# zx80_SD_12_smd_build006_4_STM32.net
KiCad netlist of a schematic drawn in EAGLE
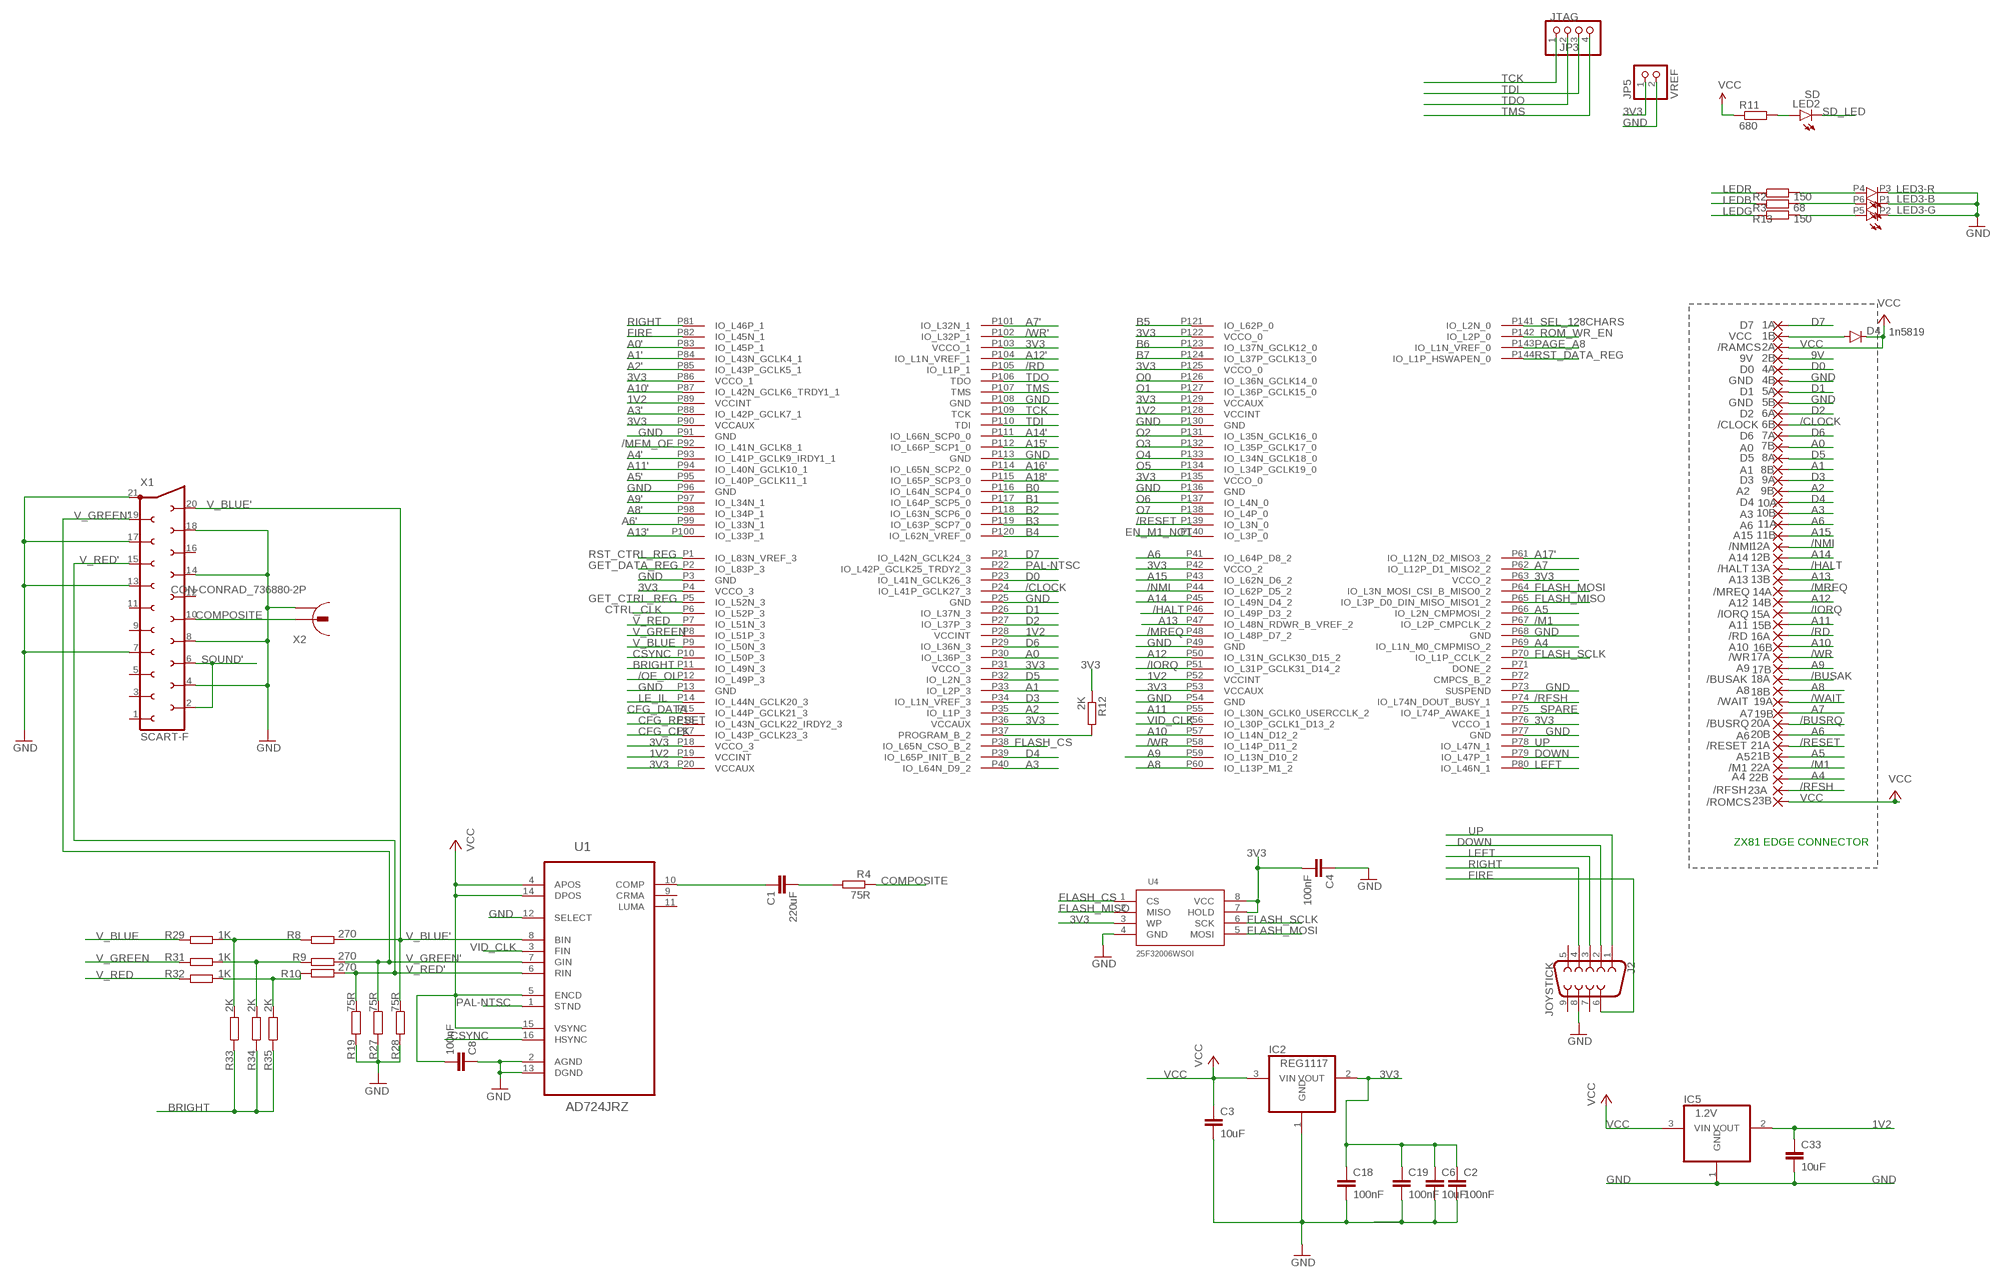
[diagram p0: schematic, sheet 1, part 1 of 2]
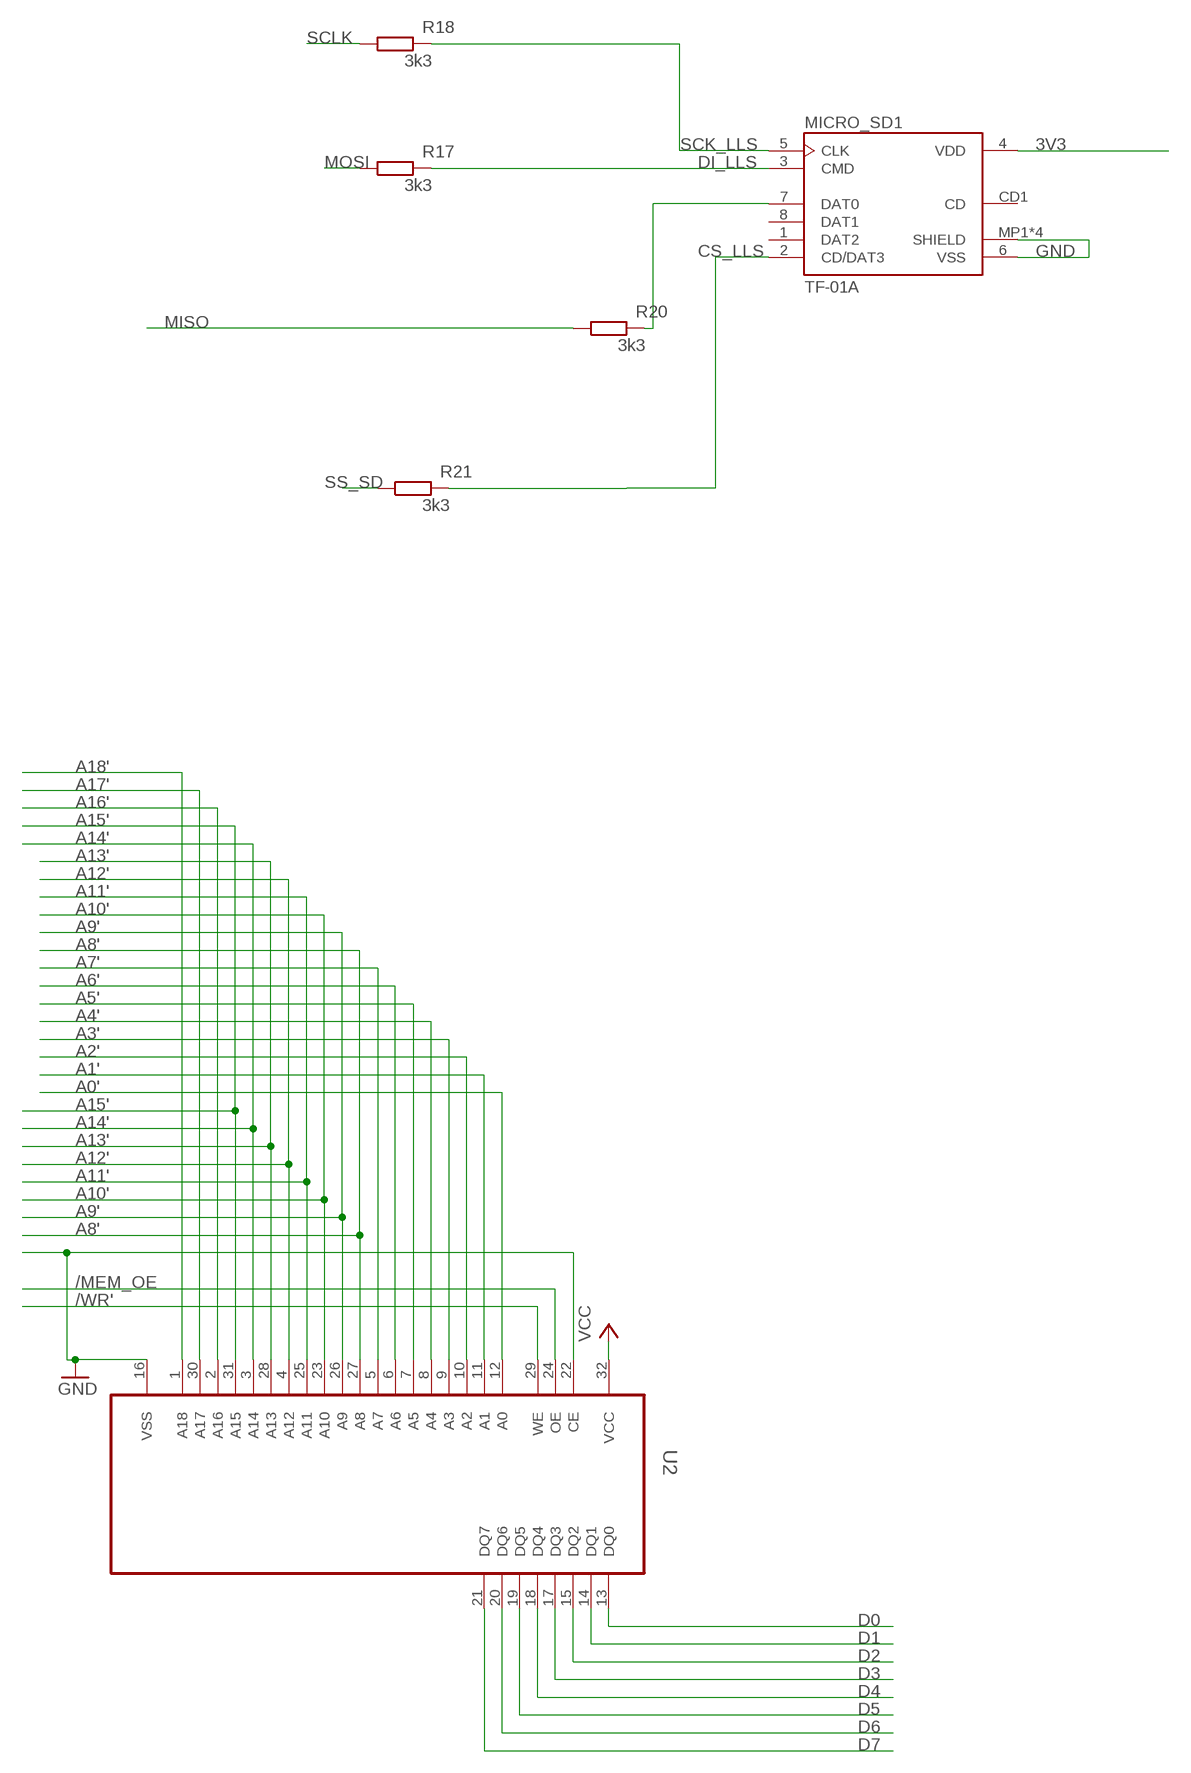
[diagram p1: schematic, sheet 1, part 2 of 2]
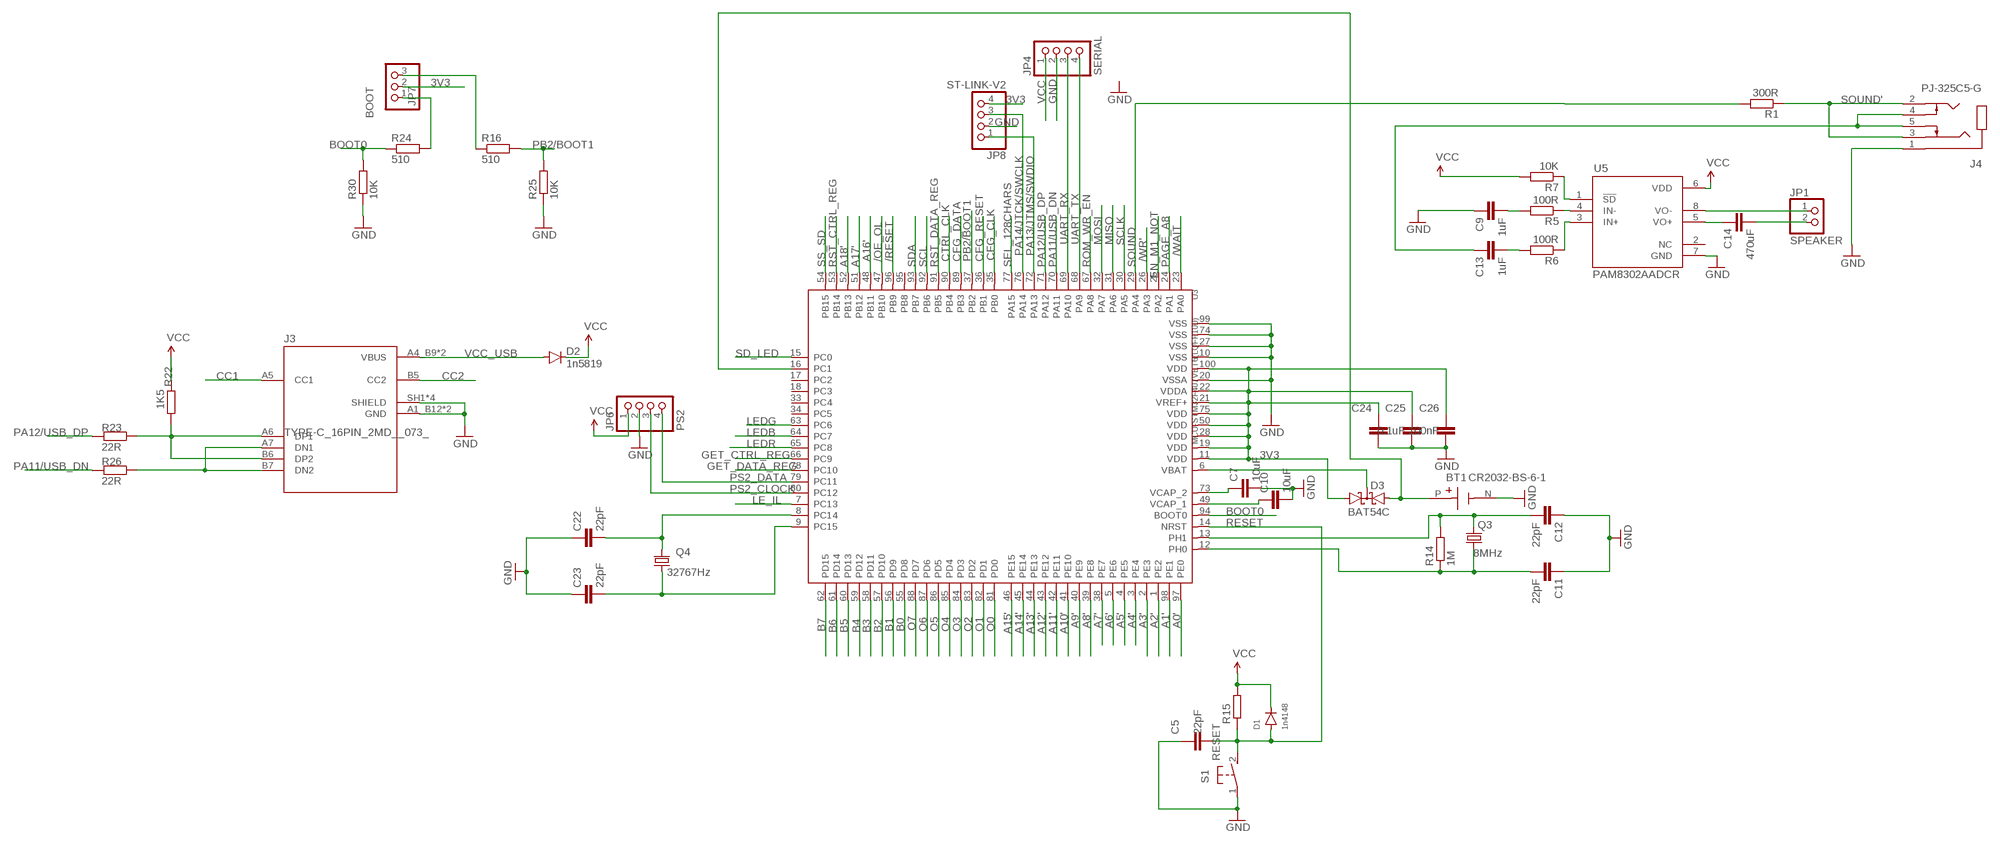
[diagram p2: schematic, sheet 2]

(export (version "E")
  (design (tool "Eeschema 10.0.6"))
  (components
    (comp (ref "BT1")
      (value "CR2032-BS-6-1")
      (footprint "eagle-import:BAT_CR2032-BS-6-1")
      (fields (field (name "MF") "Shenzhen Q&J Electronics Co. Ltd"))
      (libsource (lib "eagle-import") (part "CR2032-BS-6-1"))
    )
    (comp (ref "C5")
      (value "22pF")
      (footprint "eagle-import:C0603")
      (libsource (lib "eagle-import") (part "C-EUC0603"))
    )
    (comp (ref "C7")
      (value "10uF")
      (footprint "eagle-import:C1206")
      (libsource (lib "eagle-import") (part "C-EUC1206"))
    )
    (comp (ref "C9")
      (value "1uF")
      (footprint "eagle-import:C0603")
      (libsource (lib "eagle-import") (part "C-EUC0603"))
    )
    (comp (ref "C10")
      (value "10uF")
      (footprint "eagle-import:C1206")
      (libsource (lib "eagle-import") (part "C-EUC1206"))
    )
    (comp (ref "C11")
      (value "22pF")
      (footprint "eagle-import:C0603")
      (libsource (lib "eagle-import") (part "C-EUC0603"))
    )
    (comp (ref "C12")
      (value "22pF")
      (footprint "eagle-import:C0603")
      (libsource (lib "eagle-import") (part "C-EUC0603"))
    )
    (comp (ref "C13")
      (value "1uF")
      (footprint "eagle-import:C0603")
      (libsource (lib "eagle-import") (part "C-EUC0603"))
    )
    (comp (ref "C14")
      (value "470uF")
      (footprint "eagle-import:C0603")
      (libsource (lib "eagle-import") (part "C-EUC0603"))
    )
    (comp (ref "C22")
      (value "22pF")
      (footprint "eagle-import:C0603")
      (libsource (lib "eagle-import") (part "C-EUC0603"))
    )
    (comp (ref "C23")
      (value "22pF")
      (footprint "eagle-import:C0603")
      (libsource (lib "eagle-import") (part "C-EUC0603"))
    )
    (comp (ref "C24")
      (value "0.1uF")
      (footprint "eagle-import:C0603")
      (libsource (lib "eagle-import") (part "C-EUC0603"))
    )
    (comp (ref "C25")
      (value "0.1uF")
      (footprint "eagle-import:C0603")
      (libsource (lib "eagle-import") (part "C-EUC0603"))
    )
    (comp (ref "C26")
      (value "100nF")
      (footprint "eagle-import:C0603")
      (libsource (lib "eagle-import") (part "C-EUC0603"))
    )
    (comp (ref "D1")
      (value "1n4148")
      (footprint "eagle-import:SOD123")
      (libsource (lib "eagle-import") (part "DIODE-SOD123"))
    )
    (comp (ref "D2")
      (value "1n5819")
      (footprint "eagle-import:SOD323-W")
      (libsource (lib "eagle-import") (part "DIODE-SOD323-W"))
    )
    (comp (ref "D3")
      (value "BAT54C")
      (footprint "eagle-import:SOT23")
      (libsource (lib "eagle-import") (part "BAT54C"))
    )
    (comp (ref "J3")
      (value "TYPE-C_16PIN_2MD__073_")
      (footprint "eagle-import:SHOUHAN_TYPE-C_16PIN_2MD__073_")
      (fields (field (name "MF") "Shouhan") (field (name "MP") "TYPE-C 16PIN 2MD (073)"))
      (libsource (lib "eagle-import") (part "TYPE-C_16PIN_2MD__073_"))
    )
    (comp (ref "J4")
      (value "PJ-325C5-G")
      (footprint "eagle-import:XKB_PJ-325C5-G")
      (fields (field (name "MF") "XKB Connection"))
      (libsource (lib "eagle-import") (part "PJ-325C5-G"))
    )
    (comp (ref "JP1")
      (value "SPEAKER")
      (footprint "eagle-import:1X02")
      (libsource (lib "eagle-import") (part "PINHD-1X2"))
    )
    (comp (ref "JP4")
      (value "SERIAL")
      (footprint "eagle-import:1X04")
      (libsource (lib "eagle-import") (part "PINHD-1X4"))
    )
    (comp (ref "JP6")
      (value "PS2")
      (footprint "eagle-import:1X04")
      (libsource (lib "eagle-import") (part "PINHD-1X4"))
    )
    (comp (ref "JP7")
      (value "BOOT")
      (footprint "eagle-import:1X03")
      (libsource (lib "eagle-import") (part "PINHD-1X3"))
    )
    (comp (ref "JP8")
      (value "ST-LINK-V2")
      (footprint "eagle-import:1X04")
      (libsource (lib "eagle-import") (part "PINHD-1X4"))
    )
    (comp (ref "Q3")
      (value "8MHz")
      (footprint "eagle-import:3.2X2.5_KX-7")
      (libsource (lib "eagle-import") (part "KX-7"))
    )
    (comp (ref "Q4")
      (value "32767Hz")
      (footprint "eagle-import:3.2X1.5")
      (libsource (lib "eagle-import") (part "KX-327-NHT"))
    )
    (comp (ref "R1")
      (value "300R")
      (footprint "eagle-import:R0603")
      (libsource (lib "eagle-import") (part "R-EU_R0603"))
    )
    (comp (ref "R5")
      (value "100R")
      (footprint "eagle-import:R0603")
      (libsource (lib "eagle-import") (part "R-EU_R0603"))
    )
    (comp (ref "R6")
      (value "100R")
      (footprint "eagle-import:R0603")
      (libsource (lib "eagle-import") (part "R-EU_R0603"))
    )
    (comp (ref "R7")
      (value "10K")
      (footprint "eagle-import:R0603")
      (libsource (lib "eagle-import") (part "R-EU_R0603"))
    )
    (comp (ref "R14")
      (value "1M")
      (footprint "eagle-import:R0603")
      (libsource (lib "eagle-import") (part "R-EU_R0603"))
    )
    (comp (ref "R15")
      (value "3K3")
      (footprint "eagle-import:R0603")
      (libsource (lib "eagle-import") (part "R-EU_R0603"))
    )
    (comp (ref "R16")
      (value "510")
      (footprint "eagle-import:R0603")
      (libsource (lib "eagle-import") (part "R-EU_R0603"))
    )
    (comp (ref "R22")
      (value "1K5")
      (footprint "eagle-import:R0603")
      (libsource (lib "eagle-import") (part "R-EU_R0603"))
    )
    (comp (ref "R23")
      (value "22R")
      (footprint "eagle-import:R0603")
      (libsource (lib "eagle-import") (part "R-EU_R0603"))
    )
    (comp (ref "R24")
      (value "510")
      (footprint "eagle-import:R0603")
      (libsource (lib "eagle-import") (part "R-EU_R0603"))
    )
    (comp (ref "R25")
      (value "10K")
      (footprint "eagle-import:R0603")
      (libsource (lib "eagle-import") (part "R-EU_R0603"))
    )
    (comp (ref "R26")
      (value "22R")
      (footprint "eagle-import:R0603")
      (libsource (lib "eagle-import") (part "R-EU_R0603"))
    )
    (comp (ref "R30")
      (value "10K")
      (footprint "eagle-import:R0603")
      (libsource (lib "eagle-import") (part "R-EU_R0603"))
    )
    (comp (ref "S1")
      (value "RESET")
      (footprint "eagle-import:B3F-31XX")
      (fields (field (name "MPN") "B3F-3100"))
      (libsource (lib "eagle-import") (part "31-XX"))
    )
    (comp (ref "U3")
      (value "MCU-STM32F407VET6(LQFP100)")
      (footprint "eagle-import:LQFP100-0.5-13.8X13.8MM")
      (fields (field (name "MF") "STMicroelectronics") (field (name "MP") "STM32F407VET6"))
      (libsource (lib "eagle-import") (part "MCU-STM32F407VET6(LQFP100)"))
    )
    (comp (ref "U5")
      (value "PAM8302AADCR")
      (footprint "eagle-import:SOIC127P600X170-8N")
      (fields (field (name "MF") "Diodes Inc."))
      (libsource (lib "eagle-import") (part "PAM8302AADCR"))
    )
    (comp (ref "1A")
      (value "D7")
      (footprint "eagle-import:EDGEPIN")
      (libsource (lib "eagle-import") (part "SMD2EDGEPIN"))
    )
    (comp (ref "1B")
      (value "VCC")
      (footprint "eagle-import:EDGEPIN")
      (libsource (lib "eagle-import") (part "SMD2EDGEPIN"))
    )
    (comp (ref "2A")
      (value "/RAMCS")
      (footprint "eagle-import:EDGEPIN")
      (libsource (lib "eagle-import") (part "SMD2EDGEPIN"))
    )
    (comp (ref "2B")
      (value "9V")
      (footprint "eagle-import:EDGEPIN")
      (libsource (lib "eagle-import") (part "SMD2EDGEPIN"))
    )
    (comp (ref "4A")
      (value "D0")
      (footprint "eagle-import:EDGEPIN")
      (libsource (lib "eagle-import") (part "SMD2EDGEPIN"))
    )
    (comp (ref "4B")
      (value "GND")
      (footprint "eagle-import:EDGEPIN")
      (libsource (lib "eagle-import") (part "SMD2EDGEPIN"))
    )
    (comp (ref "5A")
      (value "D1")
      (footprint "eagle-import:EDGEPIN")
      (libsource (lib "eagle-import") (part "SMD2EDGEPIN"))
    )
    (comp (ref "5B")
      (value "GND")
      (footprint "eagle-import:EDGEPIN")
      (libsource (lib "eagle-import") (part "SMD2EDGEPIN"))
    )
    (comp (ref "6A")
      (value "D2")
      (footprint "eagle-import:EDGEPIN")
      (libsource (lib "eagle-import") (part "SMD2EDGEPIN"))
    )
    (comp (ref "6B")
      (value "/CLOCK")
      (footprint "eagle-import:EDGEPIN")
      (libsource (lib "eagle-import") (part "SMD2EDGEPIN"))
    )
    (comp (ref "7A")
      (value "D6")
      (footprint "eagle-import:EDGEPIN")
      (libsource (lib "eagle-import") (part "SMD2EDGEPIN"))
    )
    (comp (ref "7B")
      (value "A0")
      (footprint "eagle-import:EDGEPIN")
      (libsource (lib "eagle-import") (part "SMD2EDGEPIN"))
    )
    (comp (ref "8A")
      (value "D5")
      (footprint "eagle-import:EDGEPIN")
      (libsource (lib "eagle-import") (part "SMD2EDGEPIN"))
    )
    (comp (ref "8B")
      (value "A1")
      (footprint "eagle-import:EDGEPIN")
      (libsource (lib "eagle-import") (part "SMD2EDGEPIN"))
    )
    (comp (ref "9A")
      (value "D3")
      (footprint "eagle-import:EDGEPIN")
      (libsource (lib "eagle-import") (part "SMD2EDGEPIN"))
    )
    (comp (ref "9B")
      (value "A2")
      (footprint "eagle-import:EDGEPIN")
      (libsource (lib "eagle-import") (part "SMD2EDGEPIN"))
    )
    (comp (ref "10A")
      (value "D4")
      (footprint "eagle-import:EDGEPIN")
      (libsource (lib "eagle-import") (part "SMD2EDGEPIN"))
    )
    (comp (ref "10B")
      (value "A3")
      (footprint "eagle-import:EDGEPIN")
      (libsource (lib "eagle-import") (part "SMD2EDGEPIN"))
    )
    (comp (ref "11A")
      (value "A6")
      (footprint "eagle-import:EDGEPIN")
      (libsource (lib "eagle-import") (part "SMD2EDGEPIN"))
    )
    (comp (ref "11B")
      (value "A15")
      (footprint "eagle-import:EDGEPIN")
      (libsource (lib "eagle-import") (part "SMD2EDGEPIN"))
    )
    (comp (ref "12A")
      (value "/NMI")
      (footprint "eagle-import:EDGEPIN")
      (libsource (lib "eagle-import") (part "SMD2EDGEPIN"))
    )
    (comp (ref "12B")
      (value "A14")
      (footprint "eagle-import:EDGEPIN")
      (libsource (lib "eagle-import") (part "SMD2EDGEPIN"))
    )
    (comp (ref "13A")
      (value "/HALT")
      (footprint "eagle-import:EDGEPIN")
      (libsource (lib "eagle-import") (part "SMD2EDGEPIN"))
    )
    (comp (ref "13B")
      (value "A13")
      (footprint "eagle-import:EDGEPIN")
      (libsource (lib "eagle-import") (part "SMD2EDGEPIN"))
    )
    (comp (ref "14A")
      (value "/MREQ")
      (footprint "eagle-import:EDGEPIN")
      (libsource (lib "eagle-import") (part "SMD2EDGEPIN"))
    )
    (comp (ref "14B")
      (value "A12")
      (footprint "eagle-import:EDGEPIN")
      (libsource (lib "eagle-import") (part "SMD2EDGEPIN"))
    )
    (comp (ref "15A")
      (value "/IORQ")
      (footprint "eagle-import:EDGEPIN")
      (libsource (lib "eagle-import") (part "SMD2EDGEPIN"))
    )
    (comp (ref "15B")
      (value "A11")
      (footprint "eagle-import:EDGEPIN")
      (libsource (lib "eagle-import") (part "SMD2EDGEPIN"))
    )
    (comp (ref "16A")
      (value "/RD")
      (footprint "eagle-import:EDGEPIN")
      (libsource (lib "eagle-import") (part "SMD2EDGEPIN"))
    )
    (comp (ref "16B")
      (value "A10")
      (footprint "eagle-import:EDGEPIN")
      (libsource (lib "eagle-import") (part "SMD2EDGEPIN"))
    )
    (comp (ref "17A")
      (value "/WR")
      (footprint "eagle-import:EDGEPIN")
      (libsource (lib "eagle-import") (part "SMD2EDGEPIN"))
    )
    (comp (ref "17B")
      (value "A9")
      (footprint "eagle-import:EDGEPIN")
      (libsource (lib "eagle-import") (part "SMD2EDGEPIN"))
    )
    (comp (ref "18A")
      (value "/BUSAK")
      (footprint "eagle-import:EDGEPIN")
      (libsource (lib "eagle-import") (part "SMD2EDGEPIN"))
    )
    (comp (ref "18B")
      (value "A8")
      (footprint "eagle-import:EDGEPIN")
      (libsource (lib "eagle-import") (part "SMD2EDGEPIN"))
    )
    (comp (ref "19A")
      (value "/WAIT")
      (footprint "eagle-import:EDGEPIN")
      (libsource (lib "eagle-import") (part "SMD2EDGEPIN"))
    )
    (comp (ref "19B")
      (value "A7")
      (footprint "eagle-import:EDGEPIN")
      (libsource (lib "eagle-import") (part "SMD2EDGEPIN"))
    )
    (comp (ref "20A")
      (value "/BUSRQ")
      (footprint "eagle-import:EDGEPIN")
      (libsource (lib "eagle-import") (part "SMD2EDGEPIN"))
    )
    (comp (ref "20B")
      (value "A6")
      (footprint "eagle-import:EDGEPIN")
      (libsource (lib "eagle-import") (part "SMD2EDGEPIN"))
    )
    (comp (ref "21A")
      (value "/RESET")
      (footprint "eagle-import:EDGEPIN")
      (libsource (lib "eagle-import") (part "SMD2EDGEPIN"))
    )
    (comp (ref "21B")
      (value "A5")
      (footprint "eagle-import:EDGEPIN")
      (libsource (lib "eagle-import") (part "SMD2EDGEPIN"))
    )
    (comp (ref "22A")
      (value "/M1")
      (footprint "eagle-import:EDGEPIN")
      (libsource (lib "eagle-import") (part "SMD2EDGEPIN"))
    )
    (comp (ref "22B")
      (value "A4")
      (footprint "eagle-import:EDGEPIN")
      (libsource (lib "eagle-import") (part "SMD2EDGEPIN"))
    )
    (comp (ref "23A")
      (value "/RFSH")
      (footprint "eagle-import:EDGEPIN")
      (libsource (lib "eagle-import") (part "SMD2EDGEPIN"))
    )
    (comp (ref "23B")
      (value "/ROMCS")
      (footprint "eagle-import:EDGEPIN")
      (libsource (lib "eagle-import") (part "SMD2EDGEPIN"))
    )
    (comp (ref "C1")
      (value "220uF")
      (footprint "eagle-import:C0603K")
      (libsource (lib "eagle-import") (part "C-EUC0603K"))
    )
    (comp (ref "C2")
      (value "100nF")
      (footprint "eagle-import:C0603")
      (libsource (lib "eagle-import") (part "C-EUC0603"))
    )
    (comp (ref "C3")
      (value "10uF")
      (footprint "eagle-import:C0603")
      (libsource (lib "eagle-import") (part "C-EUC0603"))
    )
    (comp (ref "C4")
      (value "100nF")
      (footprint "eagle-import:C0603")
      (libsource (lib "eagle-import") (part "C-EUC0603"))
    )
    (comp (ref "C6")
      (value "10uF")
      (footprint "eagle-import:C0603")
      (libsource (lib "eagle-import") (part "C-EUC0603"))
    )
    (comp (ref "C8")
      (value "100nF")
      (footprint "eagle-import:C0603K")
      (libsource (lib "eagle-import") (part "C-EUC0603K"))
    )
    (comp (ref "C18")
      (value "100nF")
      (footprint "eagle-import:C0603")
      (libsource (lib "eagle-import") (part "C-EUC0603"))
    )
    (comp (ref "C19")
      (value "100nF")
      (footprint "eagle-import:C0603")
      (libsource (lib "eagle-import") (part "C-EUC0603"))
    )
    (comp (ref "C33")
      (value "10uF")
      (footprint "eagle-import:C0603")
      (libsource (lib "eagle-import") (part "C-EUC0603"))
    )
    (comp (ref "D4")
      (value "1n5819")
      (footprint "eagle-import:SOD323-W")
      (libsource (lib "eagle-import") (part "DIODE-SOD323-W"))
    )
    (comp (ref "IC2")
      (value "REG1117")
      (footprint "eagle-import:SOT223")
      (libsource (lib "eagle-import") (part "REG1117"))
    )
    (comp (ref "IC5")
      (value "1.2V")
      (footprint "eagle-import:SOT223")
      (fields (field (name "MPN") "REG1117"))
      (libsource (lib "eagle-import") (part "REG1117"))
    )
    (comp (ref "J2")
      (value "JOYSTICK")
      (footprint "eagle-import:DB9_MALE")
      (libsource (lib "eagle-import") (part "DB9MALE"))
    )
    (comp (ref "JP3")
      (value "JTAG")
      (footprint "eagle-import:1X04")
      (libsource (lib "eagle-import") (part "PINHD-1X4"))
    )
    (comp (ref "JP5")
      (value "VREF")
      (footprint "eagle-import:1X02")
      (libsource (lib "eagle-import") (part "PINHD-1X2"))
    )
    (comp (ref "LED2")
      (value "SD")
      (footprint "eagle-import:CHIPLED_0805")
      (libsource (lib "eagle-import") (part "LEDCHIPLED_0805"))
    )
    (comp (ref "LED3")
      (value "STATUS")
      (footprint "eagle-import:3535-PLCC6")
      (libsource (lib "eagle-import") (part "3535RGB3535RGB"))
    )
    (comp (ref "MICRO_SD1")
      (value "TF-01A")
      (footprint "eagle-import:TF-01A")
      (fields (field (name "MF") "HRO Electronics Co., Ltd."))
      (libsource (lib "eagle-import") (part "TF-01A"))
    )
    (comp (ref "R2")
      (value "150")
      (footprint "eagle-import:R0603")
      (libsource (lib "eagle-import") (part "R-EU_R0603"))
    )
    (comp (ref "R3")
      (value "68")
      (footprint "eagle-import:R0603")
      (libsource (lib "eagle-import") (part "R-EU_R0603"))
    )
    (comp (ref "R4")
      (value "75R")
      (footprint "eagle-import:R0603")
      (libsource (lib "eagle-import") (part "R-EU_R0603"))
    )
    (comp (ref "R8")
      (value "270")
      (footprint "eagle-import:R0402")
      (libsource (lib "eagle-import") (part "R-EU_R0402"))
    )
    (comp (ref "R9")
      (value "270")
      (footprint "eagle-import:R0402")
      (libsource (lib "eagle-import") (part "R-EU_R0402"))
    )
    (comp (ref "R10")
      (value "270")
      (footprint "eagle-import:R0402")
      (libsource (lib "eagle-import") (part "R-EU_R0402"))
    )
    (comp (ref "R11")
      (value "680")
      (footprint "eagle-import:R0603")
      (libsource (lib "eagle-import") (part "R-EU_R0603"))
    )
    (comp (ref "R12")
      (value "2K")
      (footprint "eagle-import:R0603")
      (libsource (lib "eagle-import") (part "R-EU_R0603"))
    )
    (comp (ref "R13")
      (value "150")
      (footprint "eagle-import:R0603")
      (libsource (lib "eagle-import") (part "R-EU_R0603"))
    )
    (comp (ref "R17")
      (value "3k3")
      (footprint "eagle-import:R0603")
      (libsource (lib "eagle-import") (part "R-EU_R0603"))
    )
    (comp (ref "R18")
      (value "3k3")
      (footprint "eagle-import:R0603")
      (libsource (lib "eagle-import") (part "R-EU_R0603"))
    )
    (comp (ref "R19")
      (value "75R")
      (footprint "eagle-import:R0402")
      (libsource (lib "eagle-import") (part "R-EU_R0402"))
    )
    (comp (ref "R20")
      (value "3k3")
      (footprint "eagle-import:R0603")
      (libsource (lib "eagle-import") (part "R-EU_R0603"))
    )
    (comp (ref "R21")
      (value "3k3")
      (footprint "eagle-import:R0603")
      (libsource (lib "eagle-import") (part "R-EU_R0603"))
    )
    (comp (ref "R27")
      (value "75R")
      (footprint "eagle-import:R0402")
      (libsource (lib "eagle-import") (part "R-EU_R0402"))
    )
    (comp (ref "R28")
      (value "75R")
      (footprint "eagle-import:R0402")
      (libsource (lib "eagle-import") (part "R-EU_R0402"))
    )
    (comp (ref "R29")
      (value "1K")
      (footprint "eagle-import:R0402")
      (libsource (lib "eagle-import") (part "R-EU_R0402"))
    )
    (comp (ref "R31")
      (value "1K")
      (footprint "eagle-import:R0402")
      (libsource (lib "eagle-import") (part "R-EU_R0402"))
    )
    (comp (ref "R32")
      (value "1K")
      (footprint "eagle-import:R0402")
      (libsource (lib "eagle-import") (part "R-EU_R0402"))
    )
    (comp (ref "R33")
      (value "2K")
      (footprint "eagle-import:R0402")
      (libsource (lib "eagle-import") (part "R-EU_R0402"))
    )
    (comp (ref "R34")
      (value "2K")
      (footprint "eagle-import:R0402")
      (libsource (lib "eagle-import") (part "R-EU_R0402"))
    )
    (comp (ref "R35")
      (value "2K")
      (footprint "eagle-import:R0402")
      (libsource (lib "eagle-import") (part "R-EU_R0402"))
    )
    (comp (ref "U$1")
      (value "XC6SLX9-2TQG144C")
      (footprint "eagle-import:TQ144")
      (fields (field (name "MF") "Xilinx Inc."))
      (libsource (lib "eagle-import") (part "XC6SLX9-2TQG144C"))
    )
    (comp (ref "U1")
      (value "AD724JRZ")
      (footprint "eagle-import:SOIC127P1032X265-16N")
      (fields (field (name "MF") "Analog Devices") (field (name "MP") "AD724JR"))
      (libsource (lib "eagle-import") (part "AD724JRZ"))
    )
    (comp (ref "U2")
      (value "AS6C4008")
      (footprint "eagle-import:SOP32-5")
      (libsource (lib "eagle-import") (part "AS6C4008-55SINSOP5"))
    )
    (comp (ref "U4")
      (value "25F32006WSOI")
      (footprint "eagle-import:SO08-EIAJ")
      (libsource (lib "eagle-import") (part "SPI_FLASH-X25XXSMD1"))
    )
    (comp (ref "X1")
      (value "SCART-F")
      (footprint "eagle-import:SCART-F")
      (libsource (lib "eagle-import") (part "SCART-F"))
    )
    (comp (ref "X2")
      (value "CON-CONRAD_736880-2P")
      (footprint "eagle-import:3P")
      (libsource (lib "eagle-import") (part "CON-CONRAD_736880-2P"))
    )
  )
  (nets
    (net (code "1") (name "1V2") (class "Default")
      (node (ref "C33") (pin "1") (pinfunction "1_1") (pintype "passive"))
      (node (ref "IC5") (pin "2") (pinfunction "VOUT_2") (pintype "output"))
      (node (ref "U$1") (pin "P128") (pinfunction "VCCINT_P128") (pintype "bidirectional"))
      (node (ref "U$1") (pin "P19") (pinfunction "VCCINT_P19") (pintype "bidirectional"))
      (node (ref "U$1") (pin "P28") (pinfunction "VCCINT_P28") (pintype "bidirectional"))
      (node (ref "U$1") (pin "P52") (pinfunction "VCCINT_P52") (pintype "bidirectional"))
      (node (ref "U$1") (pin "P89") (pinfunction "VCCINT_P89") (pintype "bidirectional"))
    )
    (net (code "2") (name "3V3") (class "Default")
      (node (ref "C18") (pin "1") (pinfunction "1_1") (pintype "passive"))
      (node (ref "C19") (pin "1") (pinfunction "1_1") (pintype "passive"))
      (node (ref "C2") (pin "1") (pinfunction "1_1") (pintype "passive"))
      (node (ref "C24") (pin "1") (pinfunction "1_1") (pintype "passive"))
      (node (ref "C25") (pin "1") (pinfunction "1_1") (pintype "passive"))
      (node (ref "C26") (pin "1") (pinfunction "1_1") (pintype "passive"))
      (node (ref "C4") (pin "2") (pinfunction "2_2") (pintype "passive"))
      (node (ref "C6") (pin "1") (pinfunction "1_1") (pintype "passive"))
      (node (ref "D3") (pin "1") (pinfunction "A1_1") (pintype "passive"))
      (node (ref "IC2") (pin "2") (pinfunction "VOUT_2") (pintype "output"))
      (node (ref "JP5") (pin "1") (pinfunction "1_1") (pintype "passive"))
      (node (ref "JP7") (pin "2") (pinfunction "2_2") (pintype "passive"))
      (node (ref "JP8") (pin "4") (pinfunction "4_4") (pintype "passive"))
      (node (ref "MICRO_SD1") (pin "4") (pinfunction "VDD_4") (pintype "power_in"))
      (node (ref "R12") (pin "1") (pinfunction "1_1") (pintype "passive"))
      (node (ref "U$1") (pin "P103") (pinfunction "VCCO_1_P103") (pintype "bidirectional"))
      (node (ref "U$1") (pin "P122") (pinfunction "VCCO_0_P122") (pintype "bidirectional"))
      (node (ref "U$1") (pin "P125") (pinfunction "VCCO_0_P125") (pintype "bidirectional"))
      (node (ref "U$1") (pin "P129") (pinfunction "VCCAUX_P129") (pintype "bidirectional"))
      (node (ref "U$1") (pin "P135") (pinfunction "VCCO_0_P135") (pintype "bidirectional"))
      (node (ref "U$1") (pin "P18") (pinfunction "VCCO_3_P18") (pintype "bidirectional"))
      (node (ref "U$1") (pin "P20") (pinfunction "VCCAUX_P20") (pintype "bidirectional"))
      (node (ref "U$1") (pin "P31") (pinfunction "VCCO_3_P31") (pintype "bidirectional"))
      (node (ref "U$1") (pin "P36") (pinfunction "VCCAUX_P36") (pintype "bidirectional"))
      (node (ref "U$1") (pin "P4") (pinfunction "VCCO_3_P4") (pintype "bidirectional"))
      (node (ref "U$1") (pin "P42") (pinfunction "VCCO_2_P42") (pintype "bidirectional"))
      (node (ref "U$1") (pin "P53") (pinfunction "VCCAUX_P53") (pintype "bidirectional"))
      (node (ref "U$1") (pin "P63") (pinfunction "VCCO_2_P63") (pintype "bidirectional"))
      (node (ref "U$1") (pin "P76") (pinfunction "VCCO_1_P76") (pintype "bidirectional"))
      (node (ref "U$1") (pin "P86") (pinfunction "VCCO_1_P86") (pintype "bidirectional"))
      (node (ref "U$1") (pin "P90") (pinfunction "VCCAUX_P90") (pintype "bidirectional"))
      (node (ref "U3") (pin "100") (pinfunction "VDD_100") (pintype "bidirectional"))
      (node (ref "U3") (pin "11") (pinfunction "VDD_11") (pintype "bidirectional"))
      (node (ref "U3") (pin "19") (pinfunction "VDD_19") (pintype "bidirectional"))
      (node (ref "U3") (pin "21") (pinfunction "VREF+_21") (pintype "bidirectional"))
      (node (ref "U3") (pin "22") (pinfunction "VDDA_22") (pintype "bidirectional"))
      (node (ref "U3") (pin "28") (pinfunction "VDD_28") (pintype "bidirectional"))
      (node (ref "U3") (pin "50") (pinfunction "VDD_50") (pintype "bidirectional"))
      (node (ref "U3") (pin "75") (pinfunction "VDD_75") (pintype "bidirectional"))
      (node (ref "U4") (pin "3") (pinfunction "WP_3") (pintype "bidirectional"))
      (node (ref "U4") (pin "7") (pinfunction "HOLD_7") (pintype "bidirectional"))
      (node (ref "U4") (pin "8") (pinfunction "VCC_8") (pintype "power_in"))
    )
    (net (code "3") (name "9V") (class "Default")
      (node (ref "2B") (pin "1") (pinfunction "P_1") (pintype "passive"))
    )
    (net (code "4") (name "A0") (class "Default")
      (node (ref "7B") (pin "1") (pinfunction "P_1") (pintype "passive"))
      (node (ref "U$1") (pin "P30") (pinfunction "IO_L36P_3_P30") (pintype "bidirectional"))
    )
    (net (code "5") (name "A0'") (class "Default")
      (node (ref "U$1") (pin "P83") (pinfunction "IO_L45P_1_P83") (pintype "bidirectional"))
      (node (ref "U2") (pin "12") (pinfunction "A0_12") (pintype "input"))
      (node (ref "U3") (pin "97") (pinfunction "PE0_97") (pintype "bidirectional"))
    )
    (net (code "6") (name "A1") (class "Default")
      (node (ref "8B") (pin "1") (pinfunction "P_1") (pintype "passive"))
      (node (ref "U$1") (pin "P33") (pinfunction "IO_L2P_3_P33") (pintype "bidirectional"))
    )
    (net (code "7") (name "A1'") (class "Default")
      (node (ref "U$1") (pin "P84") (pinfunction "IO_L43N_GCLK4_1_P84") (pintype "bidirectional"))
      (node (ref "U2") (pin "11") (pinfunction "A1_11") (pintype "input"))
      (node (ref "U3") (pin "98") (pinfunction "PE1_98") (pintype "bidirectional"))
    )
    (net (code "8") (name "A2") (class "Default")
      (node (ref "9B") (pin "1") (pinfunction "P_1") (pintype "passive"))
      (node (ref "U$1") (pin "P35") (pinfunction "IO_L1P_3_P35") (pintype "bidirectional"))
    )
    (net (code "9") (name "A2'") (class "Default")
      (node (ref "U$1") (pin "P85") (pinfunction "IO_L43P_GCLK5_1_P85") (pintype "bidirectional"))
      (node (ref "U2") (pin "10") (pinfunction "A2_10") (pintype "input"))
      (node (ref "U3") (pin "1") (pinfunction "PE2_1") (pintype "bidirectional"))
    )
    (net (code "10") (name "A3") (class "Default")
      (node (ref "10B") (pin "1") (pinfunction "P_1") (pintype "passive"))
      (node (ref "U$1") (pin "P40") (pinfunction "IO_L64N_D9_2_P40") (pintype "bidirectional"))
    )
    (net (code "11") (name "A3'") (class "Default")
      (node (ref "U$1") (pin "P88") (pinfunction "IO_L42P_GCLK7_1_P88") (pintype "bidirectional"))
      (node (ref "U2") (pin "9") (pinfunction "A3_9") (pintype "input"))
      (node (ref "U3") (pin "2") (pinfunction "PE3_2") (pintype "bidirectional"))
    )
    (net (code "12") (name "A4") (class "Default")
      (node (ref "22B") (pin "1") (pinfunction "P_1") (pintype "passive"))
      (node (ref "U$1") (pin "P69") (pinfunction "IO_L1N_M0_CMPMISO_2_P69") (pintype "bidirectional"))
    )
    (net (code "13") (name "A4'") (class "Default")
      (node (ref "U$1") (pin "P93") (pinfunction "IO_L41P_GCLK9_IRDY1_1_P93") (pintype "bidirectional"))
      (node (ref "U2") (pin "8") (pinfunction "A4_8") (pintype "input"))
      (node (ref "U3") (pin "3") (pinfunction "PE4_3") (pintype "bidirectional"))
    )
    (net (code "14") (name "A5") (class "Default")
      (node (ref "21B") (pin "1") (pinfunction "P_1") (pintype "passive"))
      (node (ref "U$1") (pin "P66") (pinfunction "IO_L2N_CMPMOSI_2_P66") (pintype "bidirectional"))
    )
    (net (code "15") (name "A5'") (class "Default")
      (node (ref "U$1") (pin "P95") (pinfunction "IO_L40P_GCLK11_1_P95") (pintype "bidirectional"))
      (node (ref "U2") (pin "7") (pinfunction "A5_7") (pintype "input"))
      (node (ref "U3") (pin "4") (pinfunction "PE5_4") (pintype "bidirectional"))
    )
    (net (code "16") (name "A6") (class "Default")
      (node (ref "11A") (pin "1") (pinfunction "P_1") (pintype "passive"))
      (node (ref "20B") (pin "1") (pinfunction "P_1") (pintype "passive"))
      (node (ref "U$1") (pin "P41") (pinfunction "IO_L64P_D8_2_P41") (pintype "bidirectional"))
    )
    (net (code "17") (name "A6'") (class "Default")
      (node (ref "U$1") (pin "P99") (pinfunction "IO_L33N_1_P99") (pintype "bidirectional"))
      (node (ref "U2") (pin "6") (pinfunction "A6_6") (pintype "input"))
      (node (ref "U3") (pin "5") (pinfunction "PE6_5") (pintype "bidirectional"))
    )
    (net (code "18") (name "A7") (class "Default")
      (node (ref "19B") (pin "1") (pinfunction "P_1") (pintype "passive"))
      (node (ref "U$1") (pin "P62") (pinfunction "IO_L12P_D1_MISO2_2_P62") (pintype "bidirectional"))
    )
    (net (code "19") (name "A7'") (class "Default")
      (node (ref "U$1") (pin "P101") (pinfunction "IO_L32N_1_P101") (pintype "bidirectional"))
      (node (ref "U2") (pin "5") (pinfunction "A7_5") (pintype "input"))
      (node (ref "U3") (pin "38") (pinfunction "PE7_38") (pintype "bidirectional"))
    )
    (net (code "20") (name "A8") (class "Default")
      (node (ref "18B") (pin "1") (pinfunction "P_1") (pintype "passive"))
      (node (ref "U$1") (pin "P60") (pinfunction "IO_L13P_M1_2_P60") (pintype "bidirectional"))
    )
    (net (code "21") (name "A8'") (class "Default")
      (node (ref "U$1") (pin "P98") (pinfunction "IO_L34P_1_P98") (pintype "bidirectional"))
      (node (ref "U2") (pin "27") (pinfunction "A8_27") (pintype "input"))
      (node (ref "U3") (pin "39") (pinfunction "PE8_39") (pintype "bidirectional"))
    )
    (net (code "22") (name "A9") (class "Default")
      (node (ref "17B") (pin "1") (pinfunction "P_1") (pintype "passive"))
      (node (ref "U$1") (pin "P59") (pinfunction "IO_L13N_D10_2_P59") (pintype "bidirectional"))
    )
    (net (code "23") (name "A9'") (class "Default")
      (node (ref "U$1") (pin "P97") (pinfunction "IO_L34N_1_P97") (pintype "bidirectional"))
      (node (ref "U2") (pin "26") (pinfunction "A9_26") (pintype "input"))
      (node (ref "U3") (pin "40") (pinfunction "PE9_40") (pintype "bidirectional"))
    )
    (net (code "24") (name "A10") (class "Default")
      (node (ref "16B") (pin "1") (pinfunction "P_1") (pintype "passive"))
      (node (ref "U$1") (pin "P57") (pinfunction "IO_L14N_D12_2_P57") (pintype "bidirectional"))
    )
    (net (code "25") (name "A10'") (class "Default")
      (node (ref "U$1") (pin "P87") (pinfunction "IO_L42N_GCLK6_TRDY1_1_P87") (pintype "bidirectional"))
      (node (ref "U2") (pin "23") (pinfunction "A10_23") (pintype "input"))
      (node (ref "U3") (pin "41") (pinfunction "PE10_41") (pintype "bidirectional"))
    )
    (net (code "26") (name "A11") (class "Default")
      (node (ref "15B") (pin "1") (pinfunction "P_1") (pintype "passive"))
      (node (ref "U$1") (pin "P55") (pinfunction "IO_L30N_GCLK0_USERCCLK_2_P55") (pintype "bidirectional"))
    )
    (net (code "27") (name "A11'") (class "Default")
      (node (ref "U$1") (pin "P94") (pinfunction "IO_L40N_GCLK10_1_P94") (pintype "bidirectional"))
      (node (ref "U2") (pin "25") (pinfunction "A11_25") (pintype "input"))
      (node (ref "U3") (pin "42") (pinfunction "PE11_42") (pintype "bidirectional"))
    )
    (net (code "28") (name "A12") (class "Default")
      (node (ref "14B") (pin "1") (pinfunction "P_1") (pintype "passive"))
      (node (ref "U$1") (pin "P50") (pinfunction "IO_L31N_GCLK30_D15_2_P50") (pintype "bidirectional"))
    )
    (net (code "29") (name "A12'") (class "Default")
      (node (ref "U$1") (pin "P104") (pinfunction "IO_L1N_VREF_1_P104") (pintype "bidirectional"))
      (node (ref "U2") (pin "4") (pinfunction "A12_4") (pintype "input"))
      (node (ref "U3") (pin "43") (pinfunction "PE12_43") (pintype "bidirectional"))
    )
    (net (code "30") (name "A13") (class "Default")
      (node (ref "13B") (pin "1") (pinfunction "P_1") (pintype "passive"))
      (node (ref "U$1") (pin "P47") (pinfunction "IO_L48N_RDWR_B_VREF_2_P47") (pintype "bidirectional"))
    )
    (net (code "31") (name "A13'") (class "Default")
      (node (ref "U$1") (pin "P100") (pinfunction "IO_L33P_1_P100") (pintype "bidirectional"))
      (node (ref "U2") (pin "28") (pinfunction "A13_28") (pintype "input"))
      (node (ref "U3") (pin "44") (pinfunction "PE13_44") (pintype "bidirectional"))
    )
    (net (code "32") (name "A14") (class "Default")
      (node (ref "12B") (pin "1") (pinfunction "P_1") (pintype "passive"))
      (node (ref "U$1") (pin "P45") (pinfunction "IO_L49N_D4_2_P45") (pintype "bidirectional"))
    )
    (net (code "33") (name "A14'") (class "Default")
      (node (ref "U$1") (pin "P111") (pinfunction "IO_L66N_SCP0_0_P111") (pintype "bidirectional"))
      (node (ref "U2") (pin "3") (pinfunction "A14_3") (pintype "input"))
      (node (ref "U3") (pin "45") (pinfunction "PE14_45") (pintype "bidirectional"))
    )
    (net (code "34") (name "A15") (class "Default")
      (node (ref "11B") (pin "1") (pinfunction "P_1") (pintype "passive"))
      (node (ref "U$1") (pin "P43") (pinfunction "IO_L62N_D6_2_P43") (pintype "bidirectional"))
    )
    (net (code "35") (name "A15'") (class "Default")
      (node (ref "U$1") (pin "P112") (pinfunction "IO_L66P_SCP1_0_P112") (pintype "bidirectional"))
      (node (ref "U2") (pin "31") (pinfunction "A15_31") (pintype "input"))
      (node (ref "U3") (pin "46") (pinfunction "PE15_46") (pintype "bidirectional"))
    )
    (net (code "36") (name "A16'") (class "Default")
      (node (ref "U$1") (pin "P114") (pinfunction "IO_L65N_SCP2_0_P114") (pintype "bidirectional"))
      (node (ref "U2") (pin "2") (pinfunction "A16_2") (pintype "input"))
      (node (ref "U3") (pin "48") (pinfunction "PB11_48") (pintype "bidirectional"))
    )
    (net (code "37") (name "A17'") (class "Default")
      (node (ref "U$1") (pin "P61") (pinfunction "IO_L12N_D2_MISO3_2_P61") (pintype "bidirectional"))
      (node (ref "U2") (pin "30") (pinfunction "A17_30") (pintype "input"))
      (node (ref "U3") (pin "51") (pinfunction "PB12_51") (pintype "bidirectional"))
    )
    (net (code "38") (name "A18'") (class "Default")
      (node (ref "U$1") (pin "P115") (pinfunction "IO_L65P_SCP3_0_P115") (pintype "bidirectional"))
      (node (ref "U2") (pin "1") (pinfunction "A18_1") (pintype "input"))
      (node (ref "U3") (pin "52") (pinfunction "PB13_52") (pintype "bidirectional"))
    )
    (net (code "39") (name "B0") (class "Default")
      (node (ref "U$1") (pin "P116") (pinfunction "IO_L64N_SCP4_0_P116") (pintype "bidirectional"))
      (node (ref "U3") (pin "55") (pinfunction "PD8_55") (pintype "bidirectional"))
    )
    (net (code "40") (name "B1") (class "Default")
      (node (ref "U$1") (pin "P117") (pinfunction "IO_L64P_SCP5_0_P117") (pintype "bidirectional"))
      (node (ref "U3") (pin "56") (pinfunction "PD9_56") (pintype "bidirectional"))
    )
    (net (code "41") (name "B2") (class "Default")
      (node (ref "U$1") (pin "P118") (pinfunction "IO_L63N_SCP6_0_P118") (pintype "bidirectional"))
      (node (ref "U3") (pin "57") (pinfunction "PD10_57") (pintype "bidirectional"))
    )
    (net (code "42") (name "B3") (class "Default")
      (node (ref "U$1") (pin "P119") (pinfunction "IO_L63P_SCP7_0_P119") (pintype "bidirectional"))
      (node (ref "U3") (pin "58") (pinfunction "PD11_58") (pintype "bidirectional"))
    )
    (net (code "43") (name "B4") (class "Default")
      (node (ref "U$1") (pin "P120") (pinfunction "IO_L62N_VREF_0_P120") (pintype "bidirectional"))
      (node (ref "U3") (pin "59") (pinfunction "PD12_59") (pintype "bidirectional"))
    )
    (net (code "44") (name "B5") (class "Default")
      (node (ref "U$1") (pin "P121") (pinfunction "IO_L62P_0_P121") (pintype "bidirectional"))
      (node (ref "U3") (pin "60") (pinfunction "PD13_60") (pintype "bidirectional"))
    )
    (net (code "45") (name "B6") (class "Default")
      (node (ref "U$1") (pin "P123") (pinfunction "IO_L37N_GCLK12_0_P123") (pintype "bidirectional"))
      (node (ref "U3") (pin "61") (pinfunction "PD14_61") (pintype "bidirectional"))
    )
    (net (code "46") (name "B7") (class "Default")
      (node (ref "U$1") (pin "P124") (pinfunction "IO_L37P_GCLK13_0_P124") (pintype "bidirectional"))
      (node (ref "U3") (pin "62") (pinfunction "PD15_62") (pintype "bidirectional"))
    )
    (net (code "47") (name "BOOT0") (class "Default")
      (node (ref "R24") (pin "1") (pinfunction "1_1") (pintype "passive"))
      (node (ref "R30") (pin "2") (pinfunction "2_2") (pintype "passive"))
      (node (ref "U3") (pin "94") (pinfunction "BOOT0_94") (pintype "bidirectional"))
    )
    (net (code "48") (name "BRIGHT") (class "Default")
      (node (ref "R33") (pin "1") (pinfunction "1_1") (pintype "passive"))
      (node (ref "R34") (pin "1") (pinfunction "1_1") (pintype "passive"))
      (node (ref "R35") (pin "1") (pinfunction "1_1") (pintype "passive"))
      (node (ref "U$1") (pin "P11") (pinfunction "IO_L49N_3_P11") (pintype "bidirectional"))
    )
    (net (code "49") (name "CC1") (class "Default")
      (node (ref "J3") (pin "A5") (pinfunction "CC1_A5") (pintype "bidirectional"))
    )
    (net (code "50") (name "CC2") (class "Default")
      (node (ref "J3") (pin "B5") (pinfunction "CC2_B5") (pintype "bidirectional"))
    )
    (net (code "51") (name "CFG_CLK") (class "Default")
      (node (ref "U$1") (pin "P17") (pinfunction "IO_L43P_GCLK23_3_P17") (pintype "bidirectional"))
      (node (ref "U3") (pin "35") (pinfunction "PB0_35") (pintype "bidirectional"))
    )
    (net (code "52") (name "CFG_DATA") (class "Default")
      (node (ref "U$1") (pin "P15") (pinfunction "IO_L44P_GCLK21_3_P15") (pintype "bidirectional"))
      (node (ref "U3") (pin "89") (pinfunction "PB3_89") (pintype "bidirectional"))
    )
    (net (code "53") (name "CFG_RESET") (class "Default")
      (node (ref "U$1") (pin "P16") (pinfunction "IO_L43N_GCLK22_IRDY2_3_P16") (pintype "bidirectional"))
      (node (ref "U3") (pin "36") (pinfunction "PB1_36") (pintype "bidirectional"))
    )
    (net (code "54") (name "COMPOSITE") (class "Default")
      (node (ref "R4") (pin "1") (pinfunction "1_1") (pintype "passive"))
      (node (ref "X1") (pin "10") (pinfunction "10_10") (pintype "passive"))
      (node (ref "X2") (pin "2") (pinfunction "1_2") (pintype "passive"))
    )
    (net (code "55") (name "CSYNC") (class "Default")
      (node (ref "U$1") (pin "P10") (pinfunction "IO_L50P_3_P10") (pintype "bidirectional"))
      (node (ref "U1") (pin "16") (pinfunction "HSYNC_16") (pintype "input"))
    )
    (net (code "56") (name "CS_LLS") (class "Default")
      (node (ref "MICRO_SD1") (pin "2") (pinfunction "CD/DAT3_2") (pintype "bidirectional"))
      (node (ref "R21") (pin "2") (pinfunction "2_2") (pintype "passive"))
    )
    (net (code "57") (name "CTRL_CLK") (class "Default")
      (node (ref "U$1") (pin "P6") (pinfunction "IO_L52P_3_P6") (pintype "bidirectional"))
      (node (ref "U3") (pin "90") (pinfunction "PB4_90") (pintype "bidirectional"))
    )
    (net (code "58") (name "D0") (class "Default")
      (node (ref "4A") (pin "1") (pinfunction "P_1") (pintype "passive"))
      (node (ref "U$1") (pin "P23") (pinfunction "IO_L41N_GCLK26_3_P23") (pintype "bidirectional"))
      (node (ref "U2") (pin "13") (pinfunction "DQ0_13") (pintype "output"))
    )
    (net (code "59") (name "D1") (class "Default")
      (node (ref "5A") (pin "1") (pinfunction "P_1") (pintype "passive"))
      (node (ref "U$1") (pin "P26") (pinfunction "IO_L37N_3_P26") (pintype "bidirectional"))
      (node (ref "U2") (pin "14") (pinfunction "DQ1_14") (pintype "output"))
    )
    (net (code "60") (name "D2") (class "Default")
      (node (ref "6A") (pin "1") (pinfunction "P_1") (pintype "passive"))
      (node (ref "U$1") (pin "P27") (pinfunction "IO_L37P_3_P27") (pintype "bidirectional"))
      (node (ref "U2") (pin "15") (pinfunction "DQ2_15") (pintype "output"))
    )
    (net (code "61") (name "D3") (class "Default")
      (node (ref "9A") (pin "1") (pinfunction "P_1") (pintype "passive"))
      (node (ref "U$1") (pin "P34") (pinfunction "IO_L1N_VREF_3_P34") (pintype "bidirectional"))
      (node (ref "U2") (pin "17") (pinfunction "DQ3_17") (pintype "output"))
    )
    (net (code "62") (name "D4") (class "Default")
      (node (ref "10A") (pin "1") (pinfunction "P_1") (pintype "passive"))
      (node (ref "U$1") (pin "P39") (pinfunction "IO_L65P_INIT_B_2_P39") (pintype "bidirectional"))
      (node (ref "U2") (pin "18") (pinfunction "DQ4_18") (pintype "output"))
    )
    (net (code "63") (name "D5") (class "Default")
      (node (ref "8A") (pin "1") (pinfunction "P_1") (pintype "passive"))
      (node (ref "U$1") (pin "P32") (pinfunction "IO_L2N_3_P32") (pintype "bidirectional"))
      (node (ref "U2") (pin "19") (pinfunction "DQ5_19") (pintype "output"))
    )
    (net (code "64") (name "D6") (class "Default")
      (node (ref "7A") (pin "1") (pinfunction "P_1") (pintype "passive"))
      (node (ref "U$1") (pin "P29") (pinfunction "IO_L36N_3_P29") (pintype "bidirectional"))
      (node (ref "U2") (pin "20") (pinfunction "DQ6_20") (pintype "output"))
    )
    (net (code "65") (name "D7") (class "Default")
      (node (ref "1A") (pin "1") (pinfunction "P_1") (pintype "passive"))
      (node (ref "U$1") (pin "P21") (pinfunction "IO_L42N_GCLK24_3_P21") (pintype "bidirectional"))
      (node (ref "U2") (pin "21") (pinfunction "DQ7_21") (pintype "output"))
    )
    (net (code "66") (name "DI_LLS") (class "Default")
      (node (ref "MICRO_SD1") (pin "3") (pinfunction "CMD_3") (pintype "bidirectional"))
      (node (ref "R17") (pin "2") (pinfunction "2_2") (pintype "passive"))
    )
    (net (code "67") (name "DOWN") (class "Default")
      (node (ref "J2") (pin "2") (pinfunction "2_2") (pintype "passive"))
      (node (ref "U$1") (pin "P79") (pinfunction "IO_L47P_1_P79") (pintype "bidirectional"))
    )
    (net (code "68") (name "EN_M1_NOT") (class "Default")
      (node (ref "U$1") (pin "P140") (pinfunction "IO_L3P_0_P140") (pintype "bidirectional"))
      (node (ref "U3") (pin "25") (pinfunction "PA2_25") (pintype "bidirectional"))
    )
    (net (code "69") (name "FIRE") (class "Default")
      (node (ref "J2") (pin "6") (pinfunction "6_6") (pintype "passive"))
      (node (ref "U$1") (pin "P82") (pinfunction "IO_L45N_1_P82") (pintype "bidirectional"))
    )
    (net (code "70") (name "FLASH_CS") (class "Default")
      (node (ref "U$1") (pin "P38") (pinfunction "IO_L65N_CSO_B_2_P38") (pintype "bidirectional"))
      (node (ref "U4") (pin "1") (pinfunction "CS_1") (pintype "bidirectional"))
    )
    (net (code "71") (name "FLASH_MISO") (class "Default")
      (node (ref "U$1") (pin "P65") (pinfunction "IO_L3P_D0_DIN_MISO_MISO1_2_P65") (pintype "bidirectional"))
      (node (ref "U4") (pin "2") (pinfunction "MISO_2") (pintype "bidirectional"))
    )
    (net (code "72") (name "FLASH_MOSI") (class "Default")
      (node (ref "U$1") (pin "P64") (pinfunction "IO_L3N_MOSI_CSI_B_MISO0_2_P64") (pintype "bidirectional"))
      (node (ref "U4") (pin "5") (pinfunction "MOSI_5") (pintype "bidirectional"))
    )
    (net (code "73") (name "FLASH_SCLK") (class "Default")
      (node (ref "U$1") (pin "P70") (pinfunction "IO_L1P_CCLK_2_P70") (pintype "bidirectional"))
      (node (ref "U4") (pin "6") (pinfunction "SCK_6") (pintype "bidirectional"))
    )
    (net (code "74") (name "GET_CTRL_REG") (class "Default")
      (node (ref "U$1") (pin "P5") (pinfunction "IO_L52N_3_P5") (pintype "bidirectional"))
      (node (ref "U3") (pin "66") (pinfunction "PC9_66") (pintype "bidirectional"))
    )
    (net (code "75") (name "GET_DATA_REG") (class "Default")
      (node (ref "U$1") (pin "P2") (pinfunction "IO_L83P_3_P2") (pintype "bidirectional"))
      (node (ref "U3") (pin "78") (pinfunction "PC10_78") (pintype "bidirectional"))
    )
    (net (code "76") (name "GND") (class "Default")
      (node (ref "4B") (pin "1") (pinfunction "P_1") (pintype "passive"))
      (node (ref "5B") (pin "1") (pinfunction "P_1") (pintype "passive"))
      (node (ref "BT1") (pin "N") (pinfunction "NEG_N") (pintype "passive"))
      (node (ref "C10") (pin "2") (pinfunction "2_2") (pintype "passive"))
      (node (ref "C11") (pin "1") (pinfunction "1_1") (pintype "passive"))
      (node (ref "C12") (pin "1") (pinfunction "1_1") (pintype "passive"))
      (node (ref "C18") (pin "2") (pinfunction "2_2") (pintype "passive"))
      (node (ref "C19") (pin "2") (pinfunction "2_2") (pintype "passive"))
      (node (ref "C2") (pin "2") (pinfunction "2_2") (pintype "passive"))
      (node (ref "C22") (pin "1") (pinfunction "1_1") (pintype "passive"))
      (node (ref "C23") (pin "1") (pinfunction "1_1") (pintype "passive"))
      (node (ref "C24") (pin "2") (pinfunction "2_2") (pintype "passive"))
      (node (ref "C25") (pin "2") (pinfunction "2_2") (pintype "passive"))
      (node (ref "C26") (pin "2") (pinfunction "2_2") (pintype "passive"))
      (node (ref "C3") (pin "2") (pinfunction "2_2") (pintype "passive"))
      (node (ref "C33") (pin "2") (pinfunction "2_2") (pintype "passive"))
      (node (ref "C4") (pin "1") (pinfunction "1_1") (pintype "passive"))
      (node (ref "C5") (pin "1") (pinfunction "1_1") (pintype "passive"))
      (node (ref "C6") (pin "2") (pinfunction "2_2") (pintype "passive"))
      (node (ref "C7") (pin "2") (pinfunction "2_2") (pintype "passive"))
      (node (ref "C8") (pin "1") (pinfunction "1_1") (pintype "passive"))
      (node (ref "C9") (pin "1") (pinfunction "1_1") (pintype "passive"))
      (node (ref "IC2") (pin "1") (pinfunction "GND_1") (pintype "power_in"))
      (node (ref "IC5") (pin "1") (pinfunction "GND_1") (pintype "power_in"))
      (node (ref "J2") (pin "8") (pinfunction "8_8") (pintype "passive"))
      (node (ref "J3") (pin "A1_B12") (pinfunction "GND_A1_B12") (pintype "power_in"))
      (node (ref "J3") (pin "B1_A12") (pinfunction "GND_B1_A12") (pintype "power_in"))
      (node (ref "J3") (pin "SH1") (pinfunction "SHIELD_SH1") (pintype "passive"))
      (node (ref "J3") (pin "SH2") (pinfunction "SHIELD_SH2") (pintype "passive"))
      (node (ref "J3") (pin "SH3") (pinfunction "SHIELD_SH3") (pintype "passive"))
      (node (ref "J3") (pin "SH4") (pinfunction "SHIELD_SH4") (pintype "passive"))
      (node (ref "J4") (pin "1") (pinfunction "1_1") (pintype "passive"))
      (node (ref "JP4") (pin "2") (pinfunction "2_2") (pintype "passive"))
      (node (ref "JP5") (pin "2") (pinfunction "2_2") (pintype "passive"))
      (node (ref "JP6") (pin "2") (pinfunction "2_2") (pintype "passive"))
      (node (ref "JP8") (pin "2") (pinfunction "2_2") (pintype "passive"))
      (node (ref "LED3") (pin "P1") (pinfunction "C_P1") (pintype "passive"))
      (node (ref "LED3") (pin "P2") (pinfunction "C_P2") (pintype "passive"))
      (node (ref "LED3") (pin "P3") (pinfunction "C_P3") (pintype "passive"))
      (node (ref "MICRO_SD1") (pin "6") (pinfunction "VSS_6") (pintype "power_in"))
      (node (ref "MICRO_SD1") (pin "MP1") (pinfunction "SHIELD_MP1") (pintype "power_in"))
      (node (ref "MICRO_SD1") (pin "MP2") (pinfunction "SHIELD_MP2") (pintype "power_in"))
      (node (ref "MICRO_SD1") (pin "MP3") (pinfunction "SHIELD_MP3") (pintype "power_in"))
      (node (ref "MICRO_SD1") (pin "MP4") (pinfunction "SHIELD_MP4") (pintype "power_in"))
      (node (ref "R19") (pin "2") (pinfunction "2_2") (pintype "passive"))
      (node (ref "R25") (pin "1") (pinfunction "1_1") (pintype "passive"))
      (node (ref "R27") (pin "2") (pinfunction "2_2") (pintype "passive"))
      (node (ref "R28") (pin "2") (pinfunction "2_2") (pintype "passive"))
      (node (ref "R30") (pin "1") (pinfunction "1_1") (pintype "passive"))
      (node (ref "S1") (pin "1") (pinfunction "P_1") (pintype "passive"))
      (node (ref "U$1") (pin "P108") (pinfunction "GND_P108") (pintype "bidirectional"))
      (node (ref "U$1") (pin "P113") (pinfunction "GND_P113") (pintype "bidirectional"))
      (node (ref "U$1") (pin "P13") (pinfunction "GND_P13") (pintype "bidirectional"))
      (node (ref "U$1") (pin "P130") (pinfunction "GND_P130") (pintype "bidirectional"))
      (node (ref "U$1") (pin "P136") (pinfunction "GND_P136") (pintype "bidirectional"))
      (node (ref "U$1") (pin "P25") (pinfunction "GND_P25") (pintype "bidirectional"))
      (node (ref "U$1") (pin "P3") (pinfunction "GND_P3") (pintype "bidirectional"))
      (node (ref "U$1") (pin "P49") (pinfunction "GND_P49") (pintype "bidirectional"))
      (node (ref "U$1") (pin "P54") (pinfunction "GND_P54") (pintype "bidirectional"))
      (node (ref "U$1") (pin "P68") (pinfunction "GND_P68") (pintype "bidirectional"))
      (node (ref "U$1") (pin "P73") (pinfunction "SUSPEND_P73") (pintype "bidirectional"))
      (node (ref "U$1") (pin "P77") (pinfunction "GND_P77") (pintype "bidirectional"))
      (node (ref "U$1") (pin "P91") (pinfunction "GND_P91") (pintype "bidirectional"))
      (node (ref "U$1") (pin "P96") (pinfunction "GND_P96") (pintype "bidirectional"))
      (node (ref "U1") (pin "12") (pinfunction "SELECT_12") (pintype "input"))
      (node (ref "U1") (pin "13") (pinfunction "DGND_13") (pintype "passive"))
      (node (ref "U1") (pin "2") (pinfunction "AGND_2") (pintype "passive"))
      (node (ref "U2") (pin "16") (pinfunction "VSS_16") (pintype "output"))
      (node (ref "U2") (pin "22") (pinfunction "CE_22") (pintype "input"))
      (node (ref "U3") (pin "10") (pinfunction "VSS_10") (pintype "bidirectional"))
      (node (ref "U3") (pin "20") (pinfunction "VSSA_20") (pintype "bidirectional"))
      (node (ref "U3") (pin "27") (pinfunction "VSS_27") (pintype "bidirectional"))
      (node (ref "U3") (pin "74") (pinfunction "VSS_74") (pintype "bidirectional"))
      (node (ref "U3") (pin "99") (pinfunction "VSS_99") (pintype "bidirectional"))
      (node (ref "U4") (pin "4") (pinfunction "GND_4") (pintype "power_in"))
      (node (ref "U5") (pin "7") (pinfunction "GND_7") (pintype "power_in"))
      (node (ref "X1") (pin "13") (pinfunction "13_13") (pintype "passive"))
      (node (ref "X1") (pin "14") (pinfunction "14_14") (pintype "passive"))
      (node (ref "X1") (pin "17") (pinfunction "17_17") (pintype "passive"))
      (node (ref "X1") (pin "18") (pinfunction "18_18") (pintype "passive"))
      (node (ref "X1") (pin "21") (pinfunction "21_21") (pintype "passive"))
      (node (ref "X1") (pin "4") (pinfunction "4_4") (pintype "passive"))
      (node (ref "X1") (pin "7") (pinfunction "7_7") (pintype "passive"))
      (node (ref "X1") (pin "8") (pinfunction "8_8") (pintype "passive"))
      (node (ref "X2") (pin "1") (pinfunction "2_1") (pintype "passive"))
    )
    (net (code "77") (name "LEDB") (class "Default")
      (node (ref "R3") (pin "1") (pinfunction "1_1") (pintype "passive"))
      (node (ref "U3") (pin "64") (pinfunction "PC7_64") (pintype "bidirectional"))
    )
    (net (code "78") (name "LEDG") (class "Default")
      (node (ref "R13") (pin "1") (pinfunction "1_1") (pintype "passive"))
      (node (ref "U3") (pin "63") (pinfunction "PC6_63") (pintype "bidirectional"))
    )
    (net (code "79") (name "LEDR") (class "Default")
      (node (ref "R2") (pin "1") (pinfunction "1_1") (pintype "passive"))
      (node (ref "U3") (pin "65") (pinfunction "PC8_65") (pintype "bidirectional"))
    )
    (net (code "80") (name "LEFT") (class "Default")
      (node (ref "J2") (pin "3") (pinfunction "3_3") (pintype "passive"))
      (node (ref "U$1") (pin "P80") (pinfunction "IO_L46N_1_P80") (pintype "bidirectional"))
    )
    (net (code "81") (name "LE_IL") (class "Default")
      (node (ref "U$1") (pin "P14") (pinfunction "IO_L44N_GCLK20_3_P14") (pintype "bidirectional"))
      (node (ref "U3") (pin "7") (pinfunction "PC13_7") (pintype "bidirectional"))
    )
    (net (code "82") (name "MISO") (class "Default")
      (node (ref "R20") (pin "1") (pinfunction "1_1") (pintype "passive"))
      (node (ref "U3") (pin "31") (pinfunction "PA6_31") (pintype "bidirectional"))
    )
    (net (code "83") (name "MOSI") (class "Default")
      (node (ref "R17") (pin "1") (pinfunction "1_1") (pintype "passive"))
      (node (ref "U3") (pin "32") (pinfunction "PA7_32") (pintype "bidirectional"))
    )
    (net (code "84") (name "Net-(1B-P)") (class "Default")
      (node (ref "1B") (pin "1") (pinfunction "P_1") (pintype "passive"))
      (node (ref "D4") (pin "A") (pinfunction "A_A") (pintype "passive"))
    )
    (net (code "85") (name "Net-(BT1-POS)") (class "Default")
      (node (ref "BT1") (pin "P") (pinfunction "POS_P") (pintype "passive"))
      (node (ref "D3") (pin "2") (pinfunction "A2_2") (pintype "passive"))
      (node (ref "U3") (pin "16") (pinfunction "PC1_16") (pintype "bidirectional"))
    )
    (net (code "86") (name "Net-(C1-Pad2)") (class "Default")
      (node (ref "C1") (pin "2") (pinfunction "2_2") (pintype "passive"))
      (node (ref "R4") (pin "2") (pinfunction "2_2") (pintype "passive"))
    )
    (net (code "87") (name "Net-(C9-Pad2)") (class "Default")
      (node (ref "C9") (pin "2") (pinfunction "2_2") (pintype "passive"))
      (node (ref "R5") (pin "2") (pinfunction "2_2") (pintype "passive"))
    )
    (net (code "88") (name "Net-(C13-Pad1)") (class "Default")
      (node (ref "C13") (pin "1") (pinfunction "1_1") (pintype "passive"))
      (node (ref "J4") (pin "4") (pinfunction "4_4") (pintype "passive"))
      (node (ref "J4") (pin "5") (pinfunction "5_5") (pintype "passive"))
    )
    (net (code "89") (name "Net-(C13-Pad2)") (class "Default")
      (node (ref "C13") (pin "2") (pinfunction "2_2") (pintype "passive"))
      (node (ref "R6") (pin "2") (pinfunction "2_2") (pintype "passive"))
    )
    (net (code "90") (name "Net-(C14-Pad2)") (class "Default")
      (node (ref "C14") (pin "2") (pinfunction "2_2") (pintype "passive"))
      (node (ref "JP1") (pin "2") (pinfunction "2_2") (pintype "passive"))
    )
    (net (code "91") (name "Net-(D3-CC)") (class "Default")
      (node (ref "D3") (pin "3") (pinfunction "CC_3") (pintype "passive"))
      (node (ref "U3") (pin "6") (pinfunction "VBAT_6") (pintype "bidirectional"))
    )
    (net (code "92") (name "Net-(J3-DN1)") (class "Default")
      (node (ref "J3") (pin "A7") (pinfunction "DN1_A7") (pintype "bidirectional"))
      (node (ref "J3") (pin "B7") (pinfunction "DN2_B7") (pintype "bidirectional"))
      (node (ref "R26") (pin "1") (pinfunction "1_1") (pintype "passive"))
    )
    (net (code "93") (name "Net-(J3-DP1)") (class "Default")
      (node (ref "J3") (pin "A6") (pinfunction "DP1_A6") (pintype "bidirectional"))
      (node (ref "J3") (pin "B6") (pinfunction "DP2_B6") (pintype "bidirectional"))
      (node (ref "R22") (pin "1") (pinfunction "1_1") (pintype "passive"))
      (node (ref "R23") (pin "1") (pinfunction "1_1") (pintype "passive"))
    )
    (net (code "94") (name "Net-(JP7-Pad1)") (class "Default")
      (node (ref "JP7") (pin "1") (pinfunction "1_1") (pintype "passive"))
      (node (ref "R24") (pin "2") (pinfunction "2_2") (pintype "passive"))
    )
    (net (code "95") (name "Net-(JP7-Pad3)") (class "Default")
      (node (ref "JP7") (pin "3") (pinfunction "3_3") (pintype "passive"))
      (node (ref "R16") (pin "1") (pinfunction "1_1") (pintype "passive"))
    )
    (net (code "96") (name "Net-(LED2-PadA)") (class "Default")
      (node (ref "LED2") (pin "A") (pinfunction "A_A") (pintype "passive"))
      (node (ref "R11") (pin "2") (pinfunction "2_2") (pintype "passive"))
    )
    (net (code "97") (name "Net-(LED3A-A)") (class "Default")
      (node (ref "LED3") (pin "P6") (pinfunction "A_P6") (pintype "passive"))
      (node (ref "R3") (pin "2") (pinfunction "2_2") (pintype "passive"))
    )
    (net (code "98") (name "Net-(LED3B-A)") (class "Default")
      (node (ref "LED3") (pin "P5") (pinfunction "A_P5") (pintype "passive"))
      (node (ref "R13") (pin "2") (pinfunction "2_2") (pintype "passive"))
    )
    (net (code "99") (name "Net-(LED3C-A)") (class "Default")
      (node (ref "LED3") (pin "P4") (pinfunction "A_P4") (pintype "passive"))
      (node (ref "R2") (pin "2") (pinfunction "2_2") (pintype "passive"))
    )
    (net (code "100") (name "Net-(MICRO_SD1-DAT0)") (class "Default")
      (node (ref "MICRO_SD1") (pin "7") (pinfunction "DAT0_7") (pintype "bidirectional"))
      (node (ref "R20") (pin "2") (pinfunction "2_2") (pintype "passive"))
    )
    (net (code "101") (name "Net-(Q3-2)") (class "Default")
      (node (ref "C12") (pin "2") (pinfunction "2_2") (pintype "passive"))
      (node (ref "Q3") (pin "3") (pinfunction "2_3") (pintype "passive"))
      (node (ref "R14") (pin "2") (pinfunction "2_2") (pintype "passive"))
      (node (ref "U3") (pin "13") (pinfunction "PH1_13") (pintype "bidirectional"))
    )
    (net (code "102") (name "Net-(R10-Pad2)") (class "Default")
      (node (ref "R10") (pin "2") (pinfunction "2_2") (pintype "passive"))
      (node (ref "R32") (pin "2") (pinfunction "2_2") (pintype "passive"))
      (node (ref "R35") (pin "2") (pinfunction "2_2") (pintype "passive"))
    )
    (net (code "103") (name "Net-(R29-Pad2)") (class "Default")
      (node (ref "R29") (pin "2") (pinfunction "2_2") (pintype "passive"))
      (node (ref "R33") (pin "2") (pinfunction "2_2") (pintype "passive"))
      (node (ref "R8") (pin "2") (pinfunction "2_2") (pintype "passive"))
    )
    (net (code "104") (name "Net-(R31-Pad2)") (class "Default")
      (node (ref "R31") (pin "2") (pinfunction "2_2") (pintype "passive"))
      (node (ref "R34") (pin "2") (pinfunction "2_2") (pintype "passive"))
      (node (ref "R9") (pin "2") (pinfunction "2_2") (pintype "passive"))
    )
    (net (code "105") (name "Net-(U$1-PROGRAM_B_2)") (class "Default")
      (node (ref "R12") (pin "2") (pinfunction "2_2") (pintype "passive"))
      (node (ref "U$1") (pin "P37") (pinfunction "PROGRAM_B_2_P37") (pintype "bidirectional"))
    )
    (net (code "106") (name "Net-(U1-COMP)") (class "Default")
      (node (ref "C1") (pin "1") (pinfunction "1_1") (pintype "passive"))
      (node (ref "U1") (pin "10") (pinfunction "COMP_10") (pintype "output"))
    )
    (net (code "107") (name "Net-(U3-PC14)") (class "Default")
      (node (ref "C22") (pin "2") (pinfunction "2_2") (pintype "passive"))
      (node (ref "Q4") (pin "2") (pinfunction "2_2") (pintype "passive"))
      (node (ref "U3") (pin "8") (pinfunction "PC14_8") (pintype "bidirectional"))
    )
    (net (code "108") (name "Net-(U3-PC15)") (class "Default")
      (node (ref "C23") (pin "2") (pinfunction "2_2") (pintype "passive"))
      (node (ref "Q4") (pin "1") (pinfunction "1_1") (pintype "passive"))
      (node (ref "U3") (pin "9") (pinfunction "PC15_9") (pintype "bidirectional"))
    )
    (net (code "109") (name "Net-(U3-PH0)") (class "Default")
      (node (ref "C11") (pin "2") (pinfunction "2_2") (pintype "passive"))
      (node (ref "Q3") (pin "1") (pinfunction "1_1") (pintype "passive"))
      (node (ref "R14") (pin "1") (pinfunction "1_1") (pintype "passive"))
      (node (ref "U3") (pin "12") (pinfunction "PH0_12") (pintype "bidirectional"))
    )
    (net (code "110") (name "Net-(U3-VCAP_1)") (class "Default")
      (node (ref "C10") (pin "1") (pinfunction "1_1") (pintype "passive"))
      (node (ref "U3") (pin "49") (pinfunction "VCAP_1_49") (pintype "bidirectional"))
    )
    (net (code "111") (name "Net-(U3-VCAP_2)") (class "Default")
      (node (ref "C7") (pin "1") (pinfunction "1_1") (pintype "passive"))
      (node (ref "U3") (pin "73") (pinfunction "VCAP_2_73") (pintype "bidirectional"))
    )
    (net (code "112") (name "Net-(U5-IN+)") (class "Default")
      (node (ref "R6") (pin "1") (pinfunction "1_1") (pintype "passive"))
      (node (ref "U5") (pin "3") (pinfunction "IN+_3") (pintype "input"))
    )
    (net (code "113") (name "Net-(U5-IN-)") (class "Default")
      (node (ref "R5") (pin "1") (pinfunction "1_1") (pintype "passive"))
      (node (ref "U5") (pin "4") (pinfunction "IN-_4") (pintype "input"))
    )
    (net (code "114") (name "Net-(U5-VO+)") (class "Default")
      (node (ref "C14") (pin "1") (pinfunction "1_1") (pintype "passive"))
      (node (ref "U5") (pin "5") (pinfunction "VO+_5") (pintype "output"))
    )
    (net (code "115") (name "Net-(U5-VO-)") (class "Default")
      (node (ref "JP1") (pin "1") (pinfunction "1_1") (pintype "passive"))
      (node (ref "U5") (pin "8") (pinfunction "VO-_8") (pintype "output"))
    )
    (net (code "116") (name "Net-(U5-~{SD})") (class "Default")
      (node (ref "R7") (pin "1") (pinfunction "1_1") (pintype "passive"))
      (node (ref "U5") (pin "1") (pinfunction "~{SD}_1") (pintype "input"))
    )
    (net (code "117") (name "O0") (class "Default")
      (node (ref "U$1") (pin "P126") (pinfunction "IO_L36N_GCLK14_0_P126") (pintype "bidirectional"))
      (node (ref "U3") (pin "81") (pinfunction "PD0_81") (pintype "bidirectional"))
    )
    (net (code "118") (name "O1") (class "Default")
      (node (ref "U$1") (pin "P127") (pinfunction "IO_L36P_GCLK15_0_P127") (pintype "bidirectional"))
      (node (ref "U3") (pin "82") (pinfunction "PD1_82") (pintype "bidirectional"))
    )
    (net (code "119") (name "O2") (class "Default")
      (node (ref "U$1") (pin "P131") (pinfunction "IO_L35N_GCLK16_0_P131") (pintype "bidirectional"))
      (node (ref "U3") (pin "83") (pinfunction "PD2_83") (pintype "bidirectional"))
    )
    (net (code "120") (name "O3") (class "Default")
      (node (ref "U$1") (pin "P132") (pinfunction "IO_L35P_GCLK17_0_P132") (pintype "bidirectional"))
      (node (ref "U3") (pin "84") (pinfunction "PD3_84") (pintype "bidirectional"))
    )
    (net (code "121") (name "O4") (class "Default")
      (node (ref "U$1") (pin "P133") (pinfunction "IO_L34N_GCLK18_0_P133") (pintype "bidirectional"))
      (node (ref "U3") (pin "85") (pinfunction "PD4_85") (pintype "bidirectional"))
    )
    (net (code "122") (name "O5") (class "Default")
      (node (ref "U$1") (pin "P134") (pinfunction "IO_L34P_GCLK19_0_P134") (pintype "bidirectional"))
      (node (ref "U3") (pin "86") (pinfunction "PD5_86") (pintype "bidirectional"))
    )
    (net (code "123") (name "O6") (class "Default")
      (node (ref "U$1") (pin "P137") (pinfunction "IO_L4N_0_P137") (pintype "bidirectional"))
      (node (ref "U3") (pin "87") (pinfunction "PD6_87") (pintype "bidirectional"))
    )
    (net (code "124") (name "O7") (class "Default")
      (node (ref "U$1") (pin "P138") (pinfunction "IO_L4P_0_P138") (pintype "bidirectional"))
      (node (ref "U3") (pin "88") (pinfunction "PD7_88") (pintype "bidirectional"))
    )
    (net (code "125") (name "PA11{slash}USB_DN") (class "Default")
      (node (ref "R26") (pin "2") (pinfunction "2_2") (pintype "passive"))
      (node (ref "U3") (pin "70") (pinfunction "PA11_70") (pintype "bidirectional"))
    )
    (net (code "126") (name "PA12{slash}USB_DP") (class "Default")
      (node (ref "R23") (pin "2") (pinfunction "2_2") (pintype "passive"))
      (node (ref "U3") (pin "71") (pinfunction "PA12_71") (pintype "bidirectional"))
    )
    (net (code "127") (name "PA13{slash}JTMS{slash}SWDIO") (class "Default")
      (node (ref "JP8") (pin "1") (pinfunction "1_1") (pintype "passive"))
      (node (ref "U3") (pin "72") (pinfunction "PA13_72") (pintype "bidirectional"))
    )
    (net (code "128") (name "PA14{slash}JTCK{slash}SWCLK") (class "Default")
      (node (ref "JP8") (pin "3") (pinfunction "3_3") (pintype "passive"))
      (node (ref "U3") (pin "76") (pinfunction "PA14_76") (pintype "bidirectional"))
    )
    (net (code "129") (name "PAGE_A8") (class "Default")
      (node (ref "U$1") (pin "P143") (pinfunction "IO_L1N_VREF_0_P143") (pintype "bidirectional"))
      (node (ref "U3") (pin "24") (pinfunction "PA1_24") (pintype "bidirectional"))
    )
    (net (code "130") (name "PAL-NTSC") (class "Default")
      (node (ref "U$1") (pin "P22") (pinfunction "IO_L42P_GCLK25_TRDY2_3_P22") (pintype "bidirectional"))
      (node (ref "U1") (pin "1") (pinfunction "STND_1") (pintype "input"))
    )
    (net (code "131") (name "PB2{slash}BOOT1") (class "Default")
      (node (ref "R16") (pin "2") (pinfunction "2_2") (pintype "passive"))
      (node (ref "R25") (pin "2") (pinfunction "2_2") (pintype "passive"))
      (node (ref "U3") (pin "37") (pinfunction "PB2_37") (pintype "bidirectional"))
    )
    (net (code "132") (name "PS2_CLOCK") (class "Default")
      (node (ref "JP6") (pin "3") (pinfunction "3_3") (pintype "passive"))
      (node (ref "U3") (pin "80") (pinfunction "PC12_80") (pintype "bidirectional"))
    )
    (net (code "133") (name "PS2_DATA") (class "Default")
      (node (ref "JP6") (pin "4") (pinfunction "4_4") (pintype "passive"))
      (node (ref "U3") (pin "79") (pinfunction "PC11_79") (pintype "bidirectional"))
    )
    (net (code "134") (name "RESET") (class "Default")
      (node (ref "C5") (pin "2") (pinfunction "2_2") (pintype "passive"))
      (node (ref "D1") (pin "A") (pinfunction "A_A") (pintype "passive"))
      (node (ref "R15") (pin "1") (pinfunction "1_1") (pintype "passive"))
      (node (ref "S1") (pin "2") (pinfunction "S_2") (pintype "passive"))
      (node (ref "U3") (pin "14") (pinfunction "NRST_14") (pintype "bidirectional"))
    )
    (net (code "135") (name "RIGHT") (class "Default")
      (node (ref "J2") (pin "4") (pinfunction "4_4") (pintype "passive"))
      (node (ref "U$1") (pin "P81") (pinfunction "IO_L46P_1_P81") (pintype "bidirectional"))
    )
    (net (code "136") (name "ROM_WR_EN") (class "Default")
      (node (ref "U$1") (pin "P142") (pinfunction "IO_L2P_0_P142") (pintype "bidirectional"))
      (node (ref "U3") (pin "67") (pinfunction "PA8_67") (pintype "bidirectional"))
    )
    (net (code "137") (name "RST_CTRL_REG") (class "Default")
      (node (ref "U$1") (pin "P1") (pinfunction "IO_L83N_VREF_3_P1") (pintype "bidirectional"))
      (node (ref "U3") (pin "53") (pinfunction "PB14_53") (pintype "bidirectional"))
    )
    (net (code "138") (name "RST_DATA_REG") (class "Default")
      (node (ref "U$1") (pin "P144") (pinfunction "IO_L1P_HSWAPEN_0_P144") (pintype "bidirectional"))
      (node (ref "U3") (pin "91") (pinfunction "PB5_91") (pintype "bidirectional"))
    )
    (net (code "139") (name "SCK_LLS") (class "Default")
      (node (ref "MICRO_SD1") (pin "5") (pinfunction "CLK_5") (pintype "bidirectional"))
      (node (ref "R18") (pin "2") (pinfunction "2_2") (pintype "passive"))
    )
    (net (code "140") (name "SCL") (class "Default")
      (node (ref "U3") (pin "92") (pinfunction "PB6_92") (pintype "bidirectional"))
    )
    (net (code "141") (name "SCLK") (class "Default")
      (node (ref "R18") (pin "1") (pinfunction "1_1") (pintype "passive"))
      (node (ref "U3") (pin "30") (pinfunction "PA5_30") (pintype "bidirectional"))
    )
    (net (code "142") (name "SDA") (class "Default")
      (node (ref "U3") (pin "93") (pinfunction "PB7_93") (pintype "bidirectional"))
    )
    (net (code "143") (name "SD_LED") (class "Default")
      (node (ref "LED2") (pin "C") (pinfunction "C_C") (pintype "passive"))
      (node (ref "U3") (pin "15") (pinfunction "PC0_15") (pintype "bidirectional"))
    )
    (net (code "144") (name "SEL_128CHARS") (class "Default")
      (node (ref "U$1") (pin "P141") (pinfunction "IO_L2N_0_P141") (pintype "bidirectional"))
      (node (ref "U3") (pin "77") (pinfunction "PA15_77") (pintype "bidirectional"))
    )
    (net (code "145") (name "SOUND") (class "Default")
      (node (ref "R1") (pin "2") (pinfunction "2_2") (pintype "passive"))
      (node (ref "U3") (pin "29") (pinfunction "PA4_29") (pintype "bidirectional"))
    )
    (net (code "146") (name "SOUND'") (class "Default")
      (node (ref "J4") (pin "2") (pinfunction "2_2") (pintype "passive"))
      (node (ref "J4") (pin "3") (pinfunction "3_3") (pintype "passive"))
      (node (ref "R1") (pin "1") (pinfunction "1_1") (pintype "passive"))
      (node (ref "X1") (pin "2") (pinfunction "2_2") (pintype "passive"))
      (node (ref "X1") (pin "6") (pinfunction "6_6") (pintype "passive"))
    )
    (net (code "147") (name "SPARE") (class "Default")
      (node (ref "U$1") (pin "P75") (pinfunction "IO_L74P_AWAKE_1_P75") (pintype "bidirectional"))
    )
    (net (code "148") (name "SS_SD") (class "Default")
      (node (ref "R21") (pin "1") (pinfunction "1_1") (pintype "passive"))
      (node (ref "U3") (pin "54") (pinfunction "PB15_54") (pintype "bidirectional"))
    )
    (net (code "149") (name "TCK") (class "Default")
      (node (ref "JP3") (pin "1") (pinfunction "1_1") (pintype "passive"))
      (node (ref "U$1") (pin "P109") (pinfunction "TCK_P109") (pintype "bidirectional"))
    )
    (net (code "150") (name "TDI") (class "Default")
      (node (ref "JP3") (pin "3") (pinfunction "3_3") (pintype "passive"))
      (node (ref "U$1") (pin "P110") (pinfunction "TDI_P110") (pintype "bidirectional"))
    )
    (net (code "151") (name "TDO") (class "Default")
      (node (ref "JP3") (pin "2") (pinfunction "2_2") (pintype "passive"))
      (node (ref "U$1") (pin "P106") (pinfunction "TDO_P106") (pintype "bidirectional"))
    )
    (net (code "152") (name "TMS") (class "Default")
      (node (ref "JP3") (pin "4") (pinfunction "4_4") (pintype "passive"))
      (node (ref "U$1") (pin "P107") (pinfunction "TMS_P107") (pintype "bidirectional"))
    )
    (net (code "153") (name "UART_RX") (class "Default")
      (node (ref "JP4") (pin "3") (pinfunction "3_3") (pintype "passive"))
      (node (ref "U3") (pin "69") (pinfunction "PA10_69") (pintype "bidirectional"))
    )
    (net (code "154") (name "UART_TX") (class "Default")
      (node (ref "JP4") (pin "4") (pinfunction "4_4") (pintype "passive"))
      (node (ref "U3") (pin "68") (pinfunction "PA9_68") (pintype "bidirectional"))
    )
    (net (code "155") (name "UP") (class "Default")
      (node (ref "J2") (pin "1") (pinfunction "1_1") (pintype "passive"))
      (node (ref "U$1") (pin "P78") (pinfunction "IO_L47N_1_P78") (pintype "bidirectional"))
    )
    (net (code "156") (name "VCC") (class "Default")
      (node (ref "23B") (pin "1") (pinfunction "P_1") (pintype "passive"))
      (node (ref "2A") (pin "1") (pinfunction "P_1") (pintype "passive"))
      (node (ref "C3") (pin "1") (pinfunction "1_1") (pintype "passive"))
      (node (ref "C8") (pin "2") (pinfunction "2_2") (pintype "passive"))
      (node (ref "D1") (pin "C") (pinfunction "C_C") (pintype "passive"))
      (node (ref "D2") (pin "C") (pinfunction "C_C") (pintype "passive"))
      (node (ref "D4") (pin "C") (pinfunction "C_C") (pintype "passive"))
      (node (ref "IC2") (pin "3") (pinfunction "VIN_3") (pintype "input"))
      (node (ref "IC5") (pin "3") (pinfunction "VIN_3") (pintype "input"))
      (node (ref "JP4") (pin "1") (pinfunction "1_1") (pintype "passive"))
      (node (ref "JP6") (pin "1") (pinfunction "1_1") (pintype "passive"))
      (node (ref "R11") (pin "1") (pinfunction "1_1") (pintype "passive"))
      (node (ref "R15") (pin "2") (pinfunction "2_2") (pintype "passive"))
      (node (ref "R22") (pin "2") (pinfunction "2_2") (pintype "passive"))
      (node (ref "R7") (pin "2") (pinfunction "2_2") (pintype "passive"))
      (node (ref "U1") (pin "14") (pinfunction "DPOS_14") (pintype "power_in"))
      (node (ref "U1") (pin "15") (pinfunction "VSYNC_15") (pintype "input"))
      (node (ref "U1") (pin "4") (pinfunction "APOS_4") (pintype "power_in"))
      (node (ref "U1") (pin "5") (pinfunction "ENCD_5") (pintype "input"))
      (node (ref "U2") (pin "32") (pinfunction "VCC_32") (pintype "power_in"))
      (node (ref "U5") (pin "6") (pinfunction "VDD_6") (pintype "power_in"))
    )
    (net (code "157") (name "VCC_USB") (class "Default")
      (node (ref "D2") (pin "A") (pinfunction "A_A") (pintype "passive"))
      (node (ref "J3") (pin "A4_B9") (pinfunction "VBUS_A4_B9") (pintype "power_in"))
      (node (ref "J3") (pin "B4_A9") (pinfunction "VBUS_B4_A9") (pintype "power_in"))
    )
    (net (code "158") (name "VID_CLK") (class "Default")
      (node (ref "U$1") (pin "P56") (pinfunction "IO_L30P_GCLK1_D13_2_P56") (pintype "bidirectional"))
      (node (ref "U1") (pin "3") (pinfunction "FIN_3") (pintype "input"))
    )
    (net (code "159") (name "V_BLUE") (class "Default")
      (node (ref "R29") (pin "1") (pinfunction "1_1") (pintype "passive"))
      (node (ref "U$1") (pin "P9") (pinfunction "IO_L50N_3_P9") (pintype "bidirectional"))
    )
    (net (code "160") (name "V_BLUE'") (class "Default")
      (node (ref "R28") (pin "1") (pinfunction "1_1") (pintype "passive"))
      (node (ref "R8") (pin "1") (pinfunction "1_1") (pintype "passive"))
      (node (ref "U1") (pin "8") (pinfunction "BIN_8") (pintype "input"))
      (node (ref "X1") (pin "20") (pinfunction "20_20") (pintype "passive"))
    )
    (net (code "161") (name "V_GREEN") (class "Default")
      (node (ref "R31") (pin "1") (pinfunction "1_1") (pintype "passive"))
      (node (ref "U$1") (pin "P8") (pinfunction "IO_L51P_3_P8") (pintype "bidirectional"))
    )
    (net (code "162") (name "V_GREEN'") (class "Default")
      (node (ref "R27") (pin "1") (pinfunction "1_1") (pintype "passive"))
      (node (ref "R9") (pin "1") (pinfunction "1_1") (pintype "passive"))
      (node (ref "U1") (pin "7") (pinfunction "GIN_7") (pintype "input"))
      (node (ref "X1") (pin "19") (pinfunction "19_19") (pintype "passive"))
    )
    (net (code "163") (name "V_RED") (class "Default")
      (node (ref "R32") (pin "1") (pinfunction "1_1") (pintype "passive"))
      (node (ref "U$1") (pin "P7") (pinfunction "IO_L51N_3_P7") (pintype "bidirectional"))
    )
    (net (code "164") (name "V_RED'") (class "Default")
      (node (ref "R10") (pin "1") (pinfunction "1_1") (pintype "passive"))
      (node (ref "R19") (pin "1") (pinfunction "1_1") (pintype "passive"))
      (node (ref "U1") (pin "6") (pinfunction "RIN_6") (pintype "input"))
      (node (ref "X1") (pin "15") (pinfunction "15_15") (pintype "passive"))
    )
    (net (code "165") (name "unconnected-(J2-Pad5)") (class "Default")
      (node (ref "J2") (pin "5") (pinfunction "5_5") (pintype "passive"))
    )
    (net (code "166") (name "unconnected-(J2-Pad7)") (class "Default")
      (node (ref "J2") (pin "7") (pinfunction "7_7") (pintype "passive"))
    )
    (net (code "167") (name "unconnected-(J2-Pad9)") (class "Default")
      (node (ref "J2") (pin "9") (pinfunction "9_9") (pintype "passive"))
    )
    (net (code "168") (name "unconnected-(MICRO_SD1-CD-PadCD1)") (class "Default")
      (node (ref "MICRO_SD1") (pin "CD1") (pinfunction "CD_CD1") (pintype "passive"))
    )
    (net (code "169") (name "unconnected-(MICRO_SD1-DAT1-Pad8)") (class "Default")
      (node (ref "MICRO_SD1") (pin "8") (pinfunction "DAT1_8") (pintype "bidirectional"))
    )
    (net (code "170") (name "unconnected-(MICRO_SD1-DAT2-Pad1)") (class "Default")
      (node (ref "MICRO_SD1") (pin "1") (pinfunction "DAT2_1") (pintype "bidirectional"))
    )
    (net (code "171") (name "unconnected-(U$1-CMPCS_B_2-PadP72)") (class "Default")
      (node (ref "U$1") (pin "P72") (pinfunction "CMPCS_B_2_P72") (pintype "bidirectional"))
    )
    (net (code "172") (name "unconnected-(U$1-DONE_2-PadP71)") (class "Default")
      (node (ref "U$1") (pin "P71") (pinfunction "DONE_2_P71") (pintype "bidirectional"))
    )
    (net (code "173") (name "unconnected-(U1-CRMA-Pad9)") (class "Default")
      (node (ref "U1") (pin "9") (pinfunction "CRMA_9") (pintype "output"))
    )
    (net (code "174") (name "unconnected-(U1-LUMA-Pad11)") (class "Default")
      (node (ref "U1") (pin "11") (pinfunction "LUMA_11") (pintype "output"))
    )
    (net (code "175") (name "unconnected-(U3-PB8-Pad95)") (class "Default")
      (node (ref "U3") (pin "95") (pinfunction "PB8_95") (pintype "bidirectional"))
    )
    (net (code "176") (name "unconnected-(U3-PC2-Pad17)") (class "Default")
      (node (ref "U3") (pin "17") (pinfunction "PC2_17") (pintype "bidirectional"))
    )
    (net (code "177") (name "unconnected-(U3-PC3-Pad18)") (class "Default")
      (node (ref "U3") (pin "18") (pinfunction "PC3_18") (pintype "bidirectional"))
    )
    (net (code "178") (name "unconnected-(U3-PC4-Pad33)") (class "Default")
      (node (ref "U3") (pin "33") (pinfunction "PC4_33") (pintype "bidirectional"))
    )
    (net (code "179") (name "unconnected-(U3-PC5-Pad34)") (class "Default")
      (node (ref "U3") (pin "34") (pinfunction "PC5_34") (pintype "bidirectional"))
    )
    (net (code "180") (name "unconnected-(U5-NC-Pad2)") (class "Default")
      (node (ref "U5") (pin "2") (pinfunction "NC_2") (pintype "no_connect"))
    )
    (net (code "181") (name "unconnected-(X1-Pad1)") (class "Default")
      (node (ref "X1") (pin "1") (pinfunction "1_1") (pintype "passive"))
    )
    (net (code "182") (name "unconnected-(X1-Pad3)") (class "Default")
      (node (ref "X1") (pin "3") (pinfunction "3_3") (pintype "passive"))
    )
    (net (code "183") (name "unconnected-(X1-Pad5)") (class "Default")
      (node (ref "X1") (pin "5") (pinfunction "5_5") (pintype "passive"))
    )
    (net (code "184") (name "unconnected-(X1-Pad9)") (class "Default")
      (node (ref "X1") (pin "9") (pinfunction "9_9") (pintype "passive"))
    )
    (net (code "185") (name "unconnected-(X1-Pad11)") (class "Default")
      (node (ref "X1") (pin "11") (pinfunction "11_11") (pintype "passive"))
    )
    (net (code "186") (name "unconnected-(X1-Pad12)") (class "Default")
      (node (ref "X1") (pin "12") (pinfunction "12_12") (pintype "passive"))
    )
    (net (code "187") (name "unconnected-(X1-Pad16)") (class "Default")
      (node (ref "X1") (pin "16") (pinfunction "16_16") (pintype "passive"))
    )
    (net (code "188") (name "{slash}BUSAK") (class "Default")
      (node (ref "18A") (pin "1") (pinfunction "P_1") (pintype "passive"))
    )
    (net (code "189") (name "{slash}BUSRQ") (class "Default")
      (node (ref "20A") (pin "1") (pinfunction "P_1") (pintype "passive"))
    )
    (net (code "190") (name "{slash}CLOCK") (class "Default")
      (node (ref "6B") (pin "1") (pinfunction "P_1") (pintype "passive"))
      (node (ref "U$1") (pin "P24") (pinfunction "IO_L41P_GCLK27_3_P24") (pintype "bidirectional"))
    )
    (net (code "191") (name "{slash}HALT") (class "Default")
      (node (ref "13A") (pin "1") (pinfunction "P_1") (pintype "passive"))
      (node (ref "U$1") (pin "P46") (pinfunction "IO_L49P_D3_2_P46") (pintype "bidirectional"))
    )
    (net (code "192") (name "{slash}IORQ") (class "Default")
      (node (ref "15A") (pin "1") (pinfunction "P_1") (pintype "passive"))
      (node (ref "U$1") (pin "P51") (pinfunction "IO_L31P_GCLK31_D14_2_P51") (pintype "bidirectional"))
    )
    (net (code "193") (name "{slash}M1") (class "Default")
      (node (ref "22A") (pin "1") (pinfunction "P_1") (pintype "passive"))
      (node (ref "U$1") (pin "P67") (pinfunction "IO_L2P_CMPCLK_2_P67") (pintype "bidirectional"))
    )
    (net (code "194") (name "{slash}MEM_OE") (class "Default")
      (node (ref "U$1") (pin "P92") (pinfunction "IO_L41N_GCLK8_1_P92") (pintype "bidirectional"))
      (node (ref "U2") (pin "24") (pinfunction "OE_24") (pintype "input"))
    )
    (net (code "195") (name "{slash}MREQ") (class "Default")
      (node (ref "14A") (pin "1") (pinfunction "P_1") (pintype "passive"))
      (node (ref "U$1") (pin "P48") (pinfunction "IO_L48P_D7_2_P48") (pintype "bidirectional"))
    )
    (net (code "196") (name "{slash}NMI") (class "Default")
      (node (ref "12A") (pin "1") (pinfunction "P_1") (pintype "passive"))
      (node (ref "U$1") (pin "P44") (pinfunction "IO_L62P_D5_2_P44") (pintype "bidirectional"))
    )
    (net (code "197") (name "{slash}OE_OL") (class "Default")
      (node (ref "U$1") (pin "P12") (pinfunction "IO_L49P_3_P12") (pintype "bidirectional"))
      (node (ref "U3") (pin "47") (pinfunction "PB10_47") (pintype "bidirectional"))
    )
    (net (code "198") (name "{slash}RD") (class "Default")
      (node (ref "16A") (pin "1") (pinfunction "P_1") (pintype "passive"))
      (node (ref "U$1") (pin "P105") (pinfunction "IO_L1P_1_P105") (pintype "bidirectional"))
    )
    (net (code "199") (name "{slash}RESET") (class "Default")
      (node (ref "21A") (pin "1") (pinfunction "P_1") (pintype "passive"))
      (node (ref "U$1") (pin "P139") (pinfunction "IO_L3N_0_P139") (pintype "bidirectional"))
      (node (ref "U3") (pin "96") (pinfunction "PB9_96") (pintype "bidirectional"))
    )
    (net (code "200") (name "{slash}RFSH") (class "Default")
      (node (ref "23A") (pin "1") (pinfunction "P_1") (pintype "passive"))
      (node (ref "U$1") (pin "P74") (pinfunction "IO_L74N_DOUT_BUSY_1_P74") (pintype "bidirectional"))
    )
    (net (code "201") (name "{slash}WAIT") (class "Default")
      (node (ref "19A") (pin "1") (pinfunction "P_1") (pintype "passive"))
      (node (ref "U3") (pin "23") (pinfunction "PA0_23") (pintype "bidirectional"))
    )
    (net (code "202") (name "{slash}WR") (class "Default")
      (node (ref "17A") (pin "1") (pinfunction "P_1") (pintype "passive"))
      (node (ref "U$1") (pin "P58") (pinfunction "IO_L14P_D11_2_P58") (pintype "bidirectional"))
    )
    (net (code "203") (name "{slash}WR'") (class "Default")
      (node (ref "U$1") (pin "P102") (pinfunction "IO_L32P_1_P102") (pintype "bidirectional"))
      (node (ref "U2") (pin "29") (pinfunction "WE_29") (pintype "input"))
      (node (ref "U3") (pin "26") (pinfunction "PA3_26") (pintype "bidirectional"))
    )
  )
)
